# Mem_Switch_V1_0.net
KiCad netlist of a schematic drawn in EAGLE
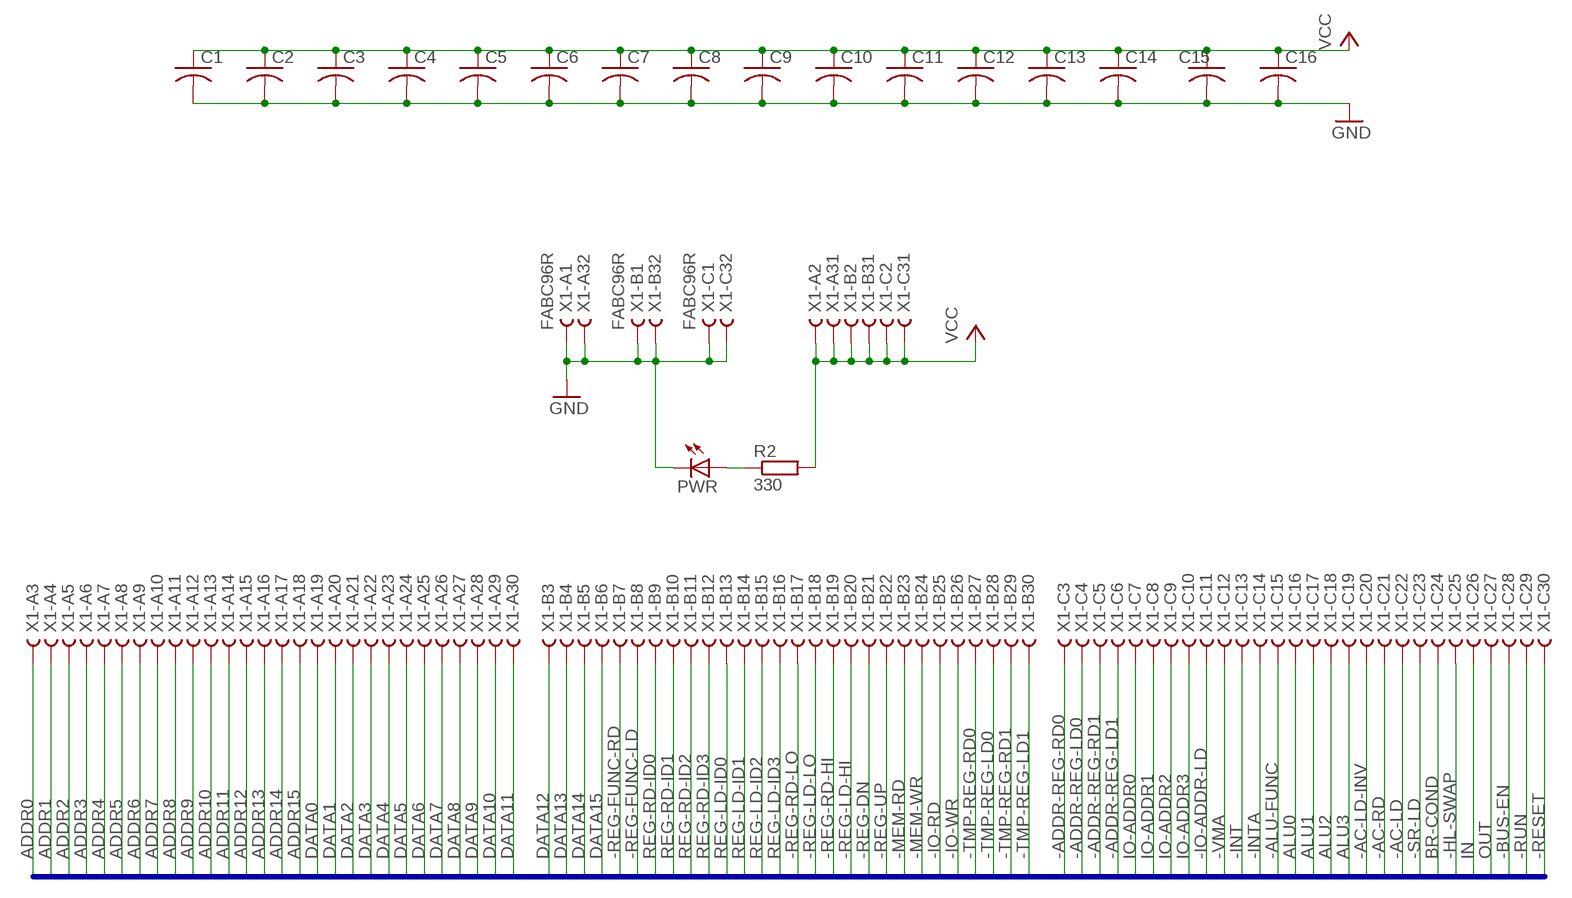
[diagram p0: schematic, sheet 1]
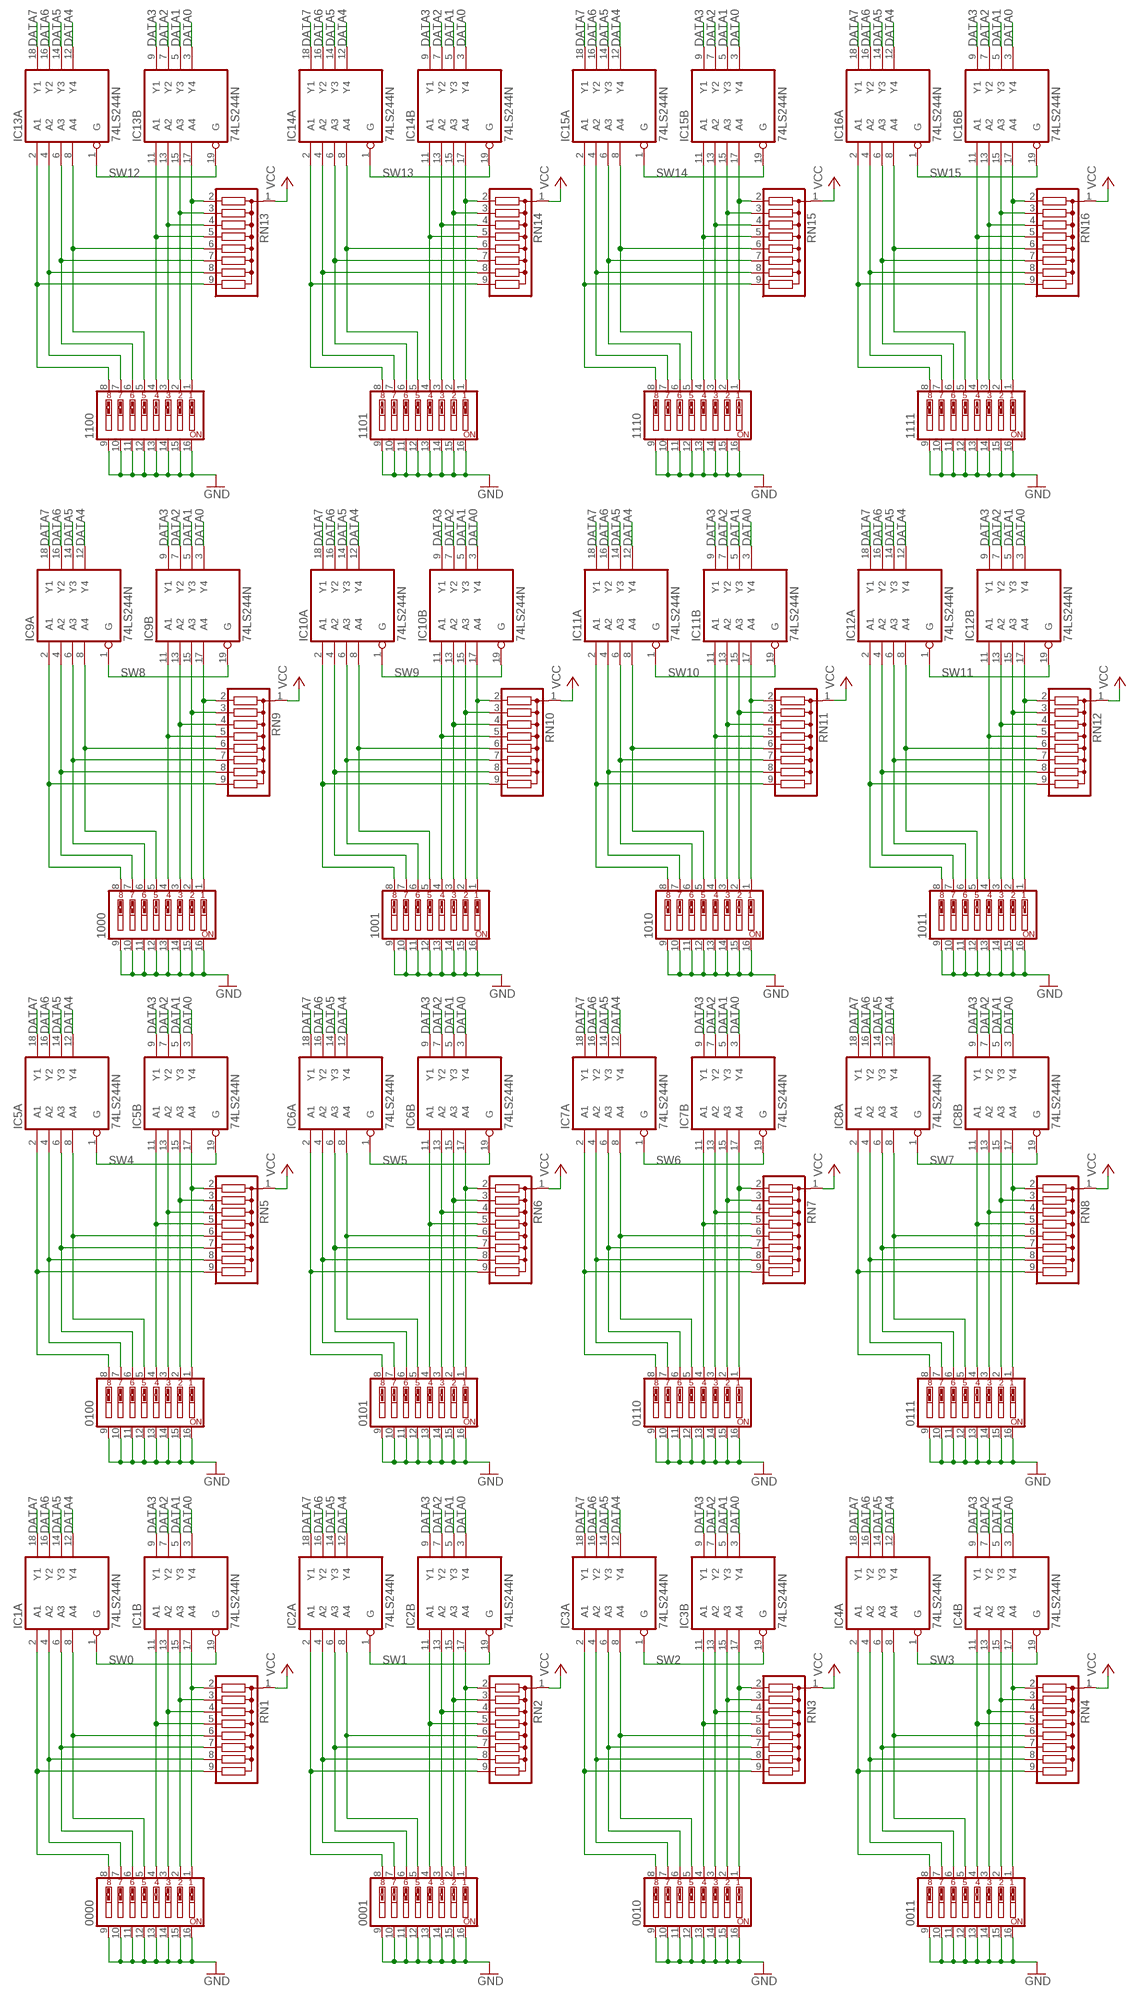
[diagram p1: schematic, sheet 2]
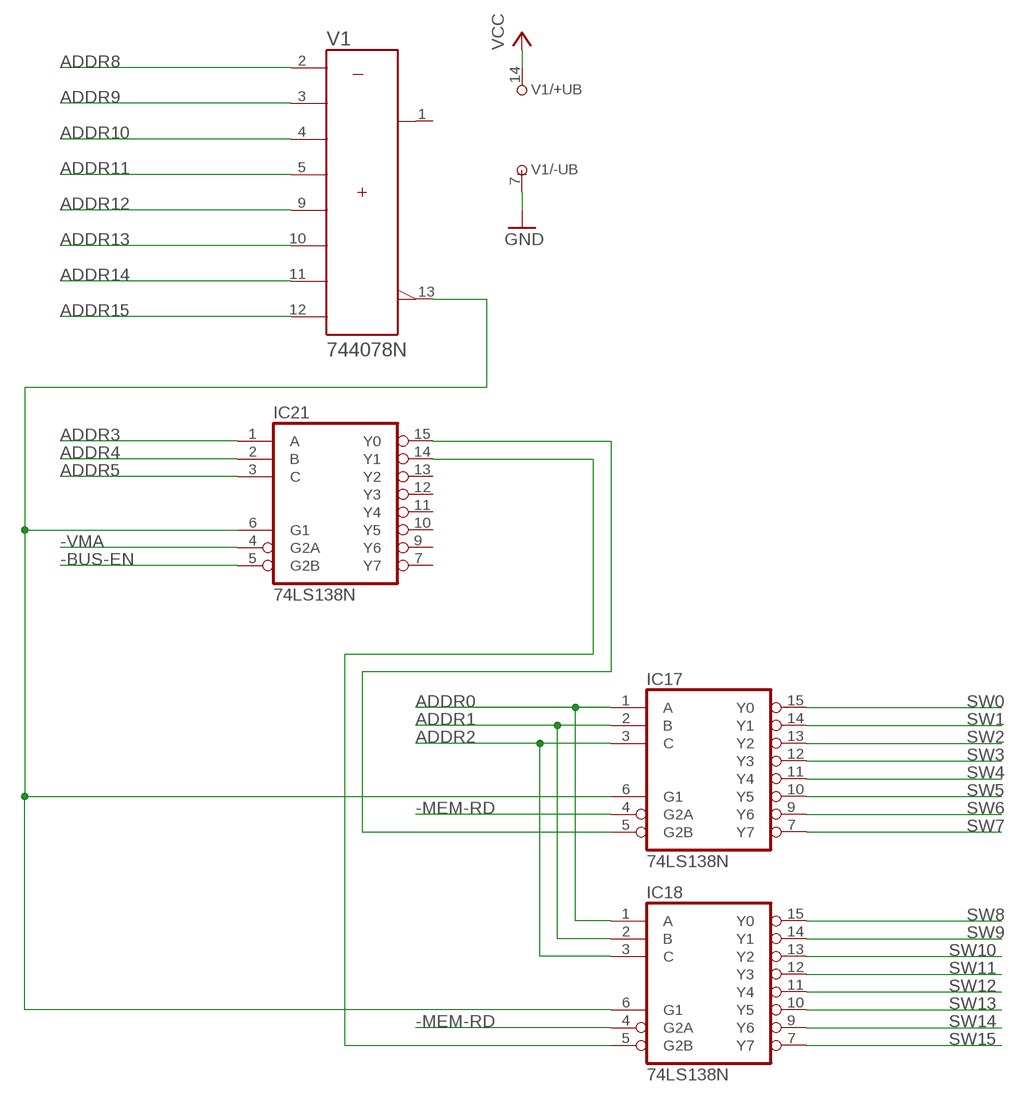
[diagram p2: schematic, sheet 3]

(export (version "E")
  (design (tool "Eeschema 10.0.6"))
  (components
    (comp (ref "C1")
      (value "C-US025-025X050")
      (footprint "eagle-import:C025-025X050")
      (libsource (lib "eagle-import") (part "C-US025-025X050"))
    )
    (comp (ref "C2")
      (value "C-US025-025X050")
      (footprint "eagle-import:C025-025X050")
      (libsource (lib "eagle-import") (part "C-US025-025X050"))
    )
    (comp (ref "C3")
      (value "C-US025-025X050")
      (footprint "eagle-import:C025-025X050")
      (libsource (lib "eagle-import") (part "C-US025-025X050"))
    )
    (comp (ref "C4")
      (value "C-US025-025X050")
      (footprint "eagle-import:C025-025X050")
      (libsource (lib "eagle-import") (part "C-US025-025X050"))
    )
    (comp (ref "C5")
      (value "C-US025-025X050")
      (footprint "eagle-import:C025-025X050")
      (libsource (lib "eagle-import") (part "C-US025-025X050"))
    )
    (comp (ref "C6")
      (value "C-US025-025X050")
      (footprint "eagle-import:C025-025X050")
      (libsource (lib "eagle-import") (part "C-US025-025X050"))
    )
    (comp (ref "C7")
      (value "C-US025-025X050")
      (footprint "eagle-import:C025-025X050")
      (libsource (lib "eagle-import") (part "C-US025-025X050"))
    )
    (comp (ref "C8")
      (value "C-US025-025X050")
      (footprint "eagle-import:C025-025X050")
      (libsource (lib "eagle-import") (part "C-US025-025X050"))
    )
    (comp (ref "C9")
      (value "C-US025-025X050")
      (footprint "eagle-import:C025-025X050")
      (libsource (lib "eagle-import") (part "C-US025-025X050"))
    )
    (comp (ref "C10")
      (value "C-US025-025X050")
      (footprint "eagle-import:C025-025X050")
      (libsource (lib "eagle-import") (part "C-US025-025X050"))
    )
    (comp (ref "C11")
      (value "C-US025-025X050")
      (footprint "eagle-import:C025-025X050")
      (libsource (lib "eagle-import") (part "C-US025-025X050"))
    )
    (comp (ref "C12")
      (value "C-US025-025X050")
      (footprint "eagle-import:C025-025X050")
      (libsource (lib "eagle-import") (part "C-US025-025X050"))
    )
    (comp (ref "C13")
      (value "C-US025-025X050")
      (footprint "eagle-import:C025-025X050")
      (libsource (lib "eagle-import") (part "C-US025-025X050"))
    )
    (comp (ref "C14")
      (value "C-US025-025X050")
      (footprint "eagle-import:C025-025X050")
      (libsource (lib "eagle-import") (part "C-US025-025X050"))
    )
    (comp (ref "C15")
      (value "C-US025-025X050")
      (footprint "eagle-import:C025-025X050")
      (libsource (lib "eagle-import") (part "C-US025-025X050"))
    )
    (comp (ref "C16")
      (value "C-US025-025X050")
      (footprint "eagle-import:C025-025X050")
      (libsource (lib "eagle-import") (part "C-US025-025X050"))
    )
    (comp (ref "PWR")
      (value "LED5MM")
      (footprint "eagle-import:LED5MM")
      (libsource (lib "eagle-import") (part "LED5MM"))
    )
    (comp (ref "R2")
      (value "330")
      (footprint "eagle-import:0207_10")
      (libsource (lib "eagle-import") (part "R0207/10"))
    )
    (comp (ref "X1")
      (value "FABC96R")
      (footprint "eagle-import:FABC96R")
      (libsource (lib "eagle-import") (part "FABC96R"))
    )
    (comp (ref "0000")
      (value "SW_DIP-8")
      (footprint "eagle-import:EDG-08")
      (libsource (lib "eagle-import") (part "SW_DIP-8"))
    )
    (comp (ref "0001")
      (value "SW_DIP-8")
      (footprint "eagle-import:EDG-08")
      (libsource (lib "eagle-import") (part "SW_DIP-8"))
    )
    (comp (ref "0010")
      (value "SW_DIP-8")
      (footprint "eagle-import:EDG-08")
      (libsource (lib "eagle-import") (part "SW_DIP-8"))
    )
    (comp (ref "0011")
      (value "SW_DIP-8")
      (footprint "eagle-import:EDG-08")
      (libsource (lib "eagle-import") (part "SW_DIP-8"))
    )
    (comp (ref "0100")
      (value "SW_DIP-8")
      (footprint "eagle-import:EDG-08")
      (libsource (lib "eagle-import") (part "SW_DIP-8"))
    )
    (comp (ref "0101")
      (value "SW_DIP-8")
      (footprint "eagle-import:EDG-08")
      (libsource (lib "eagle-import") (part "SW_DIP-8"))
    )
    (comp (ref "0110")
      (value "SW_DIP-8")
      (footprint "eagle-import:EDG-08")
      (libsource (lib "eagle-import") (part "SW_DIP-8"))
    )
    (comp (ref "0111")
      (value "SW_DIP-8")
      (footprint "eagle-import:EDG-08")
      (libsource (lib "eagle-import") (part "SW_DIP-8"))
    )
    (comp (ref "1000")
      (value "SW_DIP-8")
      (footprint "eagle-import:EDG-08")
      (libsource (lib "eagle-import") (part "SW_DIP-8"))
    )
    (comp (ref "1001")
      (value "SW_DIP-8")
      (footprint "eagle-import:EDG-08")
      (libsource (lib "eagle-import") (part "SW_DIP-8"))
    )
    (comp (ref "1010")
      (value "SW_DIP-8")
      (footprint "eagle-import:EDG-08")
      (libsource (lib "eagle-import") (part "SW_DIP-8"))
    )
    (comp (ref "1011")
      (value "SW_DIP-8")
      (footprint "eagle-import:EDG-08")
      (libsource (lib "eagle-import") (part "SW_DIP-8"))
    )
    (comp (ref "1100")
      (value "SW_DIP-8")
      (footprint "eagle-import:EDG-08")
      (libsource (lib "eagle-import") (part "SW_DIP-8"))
    )
    (comp (ref "1101")
      (value "SW_DIP-8")
      (footprint "eagle-import:EDG-08")
      (libsource (lib "eagle-import") (part "SW_DIP-8"))
    )
    (comp (ref "1110")
      (value "SW_DIP-8")
      (footprint "eagle-import:EDG-08")
      (libsource (lib "eagle-import") (part "SW_DIP-8"))
    )
    (comp (ref "1111")
      (value "SW_DIP-8")
      (footprint "eagle-import:EDG-08")
      (libsource (lib "eagle-import") (part "SW_DIP-8"))
    )
    (comp (ref "IC1")
      (value "74LS244N")
      (footprint "eagle-import:DIL20")
      (libsource (lib "eagle-import") (part "74xx-us_88_74244NLS"))
    )
    (comp (ref "IC2")
      (value "74LS244N")
      (footprint "eagle-import:DIL20")
      (libsource (lib "eagle-import") (part "74xx-us_88_74244NLS"))
    )
    (comp (ref "IC3")
      (value "74LS244N")
      (footprint "eagle-import:DIL20")
      (libsource (lib "eagle-import") (part "74xx-us_88_74244NLS"))
    )
    (comp (ref "IC4")
      (value "74LS244N")
      (footprint "eagle-import:DIL20")
      (libsource (lib "eagle-import") (part "74xx-us_88_74244NLS"))
    )
    (comp (ref "IC5")
      (value "74LS244N")
      (footprint "eagle-import:DIL20")
      (libsource (lib "eagle-import") (part "74xx-us_88_74244NLS"))
    )
    (comp (ref "IC6")
      (value "74LS244N")
      (footprint "eagle-import:DIL20")
      (libsource (lib "eagle-import") (part "74xx-us_88_74244NLS"))
    )
    (comp (ref "IC7")
      (value "74LS244N")
      (footprint "eagle-import:DIL20")
      (libsource (lib "eagle-import") (part "74xx-us_88_74244NLS"))
    )
    (comp (ref "IC8")
      (value "74LS244N")
      (footprint "eagle-import:DIL20")
      (libsource (lib "eagle-import") (part "74xx-us_88_74244NLS"))
    )
    (comp (ref "IC9")
      (value "74LS244N")
      (footprint "eagle-import:DIL20")
      (libsource (lib "eagle-import") (part "74xx-us_88_74244NLS"))
    )
    (comp (ref "IC10")
      (value "74LS244N")
      (footprint "eagle-import:DIL20")
      (libsource (lib "eagle-import") (part "74xx-us_88_74244NLS"))
    )
    (comp (ref "IC11")
      (value "74LS244N")
      (footprint "eagle-import:DIL20")
      (libsource (lib "eagle-import") (part "74xx-us_88_74244NLS"))
    )
    (comp (ref "IC12")
      (value "74LS244N")
      (footprint "eagle-import:DIL20")
      (libsource (lib "eagle-import") (part "74xx-us_88_74244NLS"))
    )
    (comp (ref "IC13")
      (value "74LS244N")
      (footprint "eagle-import:DIL20")
      (libsource (lib "eagle-import") (part "74xx-us_88_74244NLS"))
    )
    (comp (ref "IC14")
      (value "74LS244N")
      (footprint "eagle-import:DIL20")
      (libsource (lib "eagle-import") (part "74xx-us_88_74244NLS"))
    )
    (comp (ref "IC15")
      (value "74LS244N")
      (footprint "eagle-import:DIL20")
      (libsource (lib "eagle-import") (part "74xx-us_88_74244NLS"))
    )
    (comp (ref "IC16")
      (value "74LS244N")
      (footprint "eagle-import:DIL20")
      (libsource (lib "eagle-import") (part "74xx-us_88_74244NLS"))
    )
    (comp (ref "RN1")
      (value "G08R")
      (footprint "eagle-import:SIL9")
      (libsource (lib "eagle-import") (part "G08R"))
    )
    (comp (ref "RN2")
      (value "G08R")
      (footprint "eagle-import:SIL9")
      (libsource (lib "eagle-import") (part "G08R"))
    )
    (comp (ref "RN3")
      (value "G08R")
      (footprint "eagle-import:SIL9")
      (libsource (lib "eagle-import") (part "G08R"))
    )
    (comp (ref "RN4")
      (value "G08R")
      (footprint "eagle-import:SIL9")
      (libsource (lib "eagle-import") (part "G08R"))
    )
    (comp (ref "RN5")
      (value "G08R")
      (footprint "eagle-import:SIL9")
      (libsource (lib "eagle-import") (part "G08R"))
    )
    (comp (ref "RN6")
      (value "G08R")
      (footprint "eagle-import:SIL9")
      (libsource (lib "eagle-import") (part "G08R"))
    )
    (comp (ref "RN7")
      (value "G08R")
      (footprint "eagle-import:SIL9")
      (libsource (lib "eagle-import") (part "G08R"))
    )
    (comp (ref "RN8")
      (value "G08R")
      (footprint "eagle-import:SIL9")
      (libsource (lib "eagle-import") (part "G08R"))
    )
    (comp (ref "RN9")
      (value "G08R")
      (footprint "eagle-import:SIL9")
      (libsource (lib "eagle-import") (part "G08R"))
    )
    (comp (ref "RN10")
      (value "G08R")
      (footprint "eagle-import:SIL9")
      (libsource (lib "eagle-import") (part "G08R"))
    )
    (comp (ref "RN11")
      (value "G08R")
      (footprint "eagle-import:SIL9")
      (libsource (lib "eagle-import") (part "G08R"))
    )
    (comp (ref "RN12")
      (value "G08R")
      (footprint "eagle-import:SIL9")
      (libsource (lib "eagle-import") (part "G08R"))
    )
    (comp (ref "RN13")
      (value "G08R")
      (footprint "eagle-import:SIL9")
      (libsource (lib "eagle-import") (part "G08R"))
    )
    (comp (ref "RN14")
      (value "G08R")
      (footprint "eagle-import:SIL9")
      (libsource (lib "eagle-import") (part "G08R"))
    )
    (comp (ref "RN15")
      (value "G08R")
      (footprint "eagle-import:SIL9")
      (libsource (lib "eagle-import") (part "G08R"))
    )
    (comp (ref "RN16")
      (value "G08R")
      (footprint "eagle-import:SIL9")
      (libsource (lib "eagle-import") (part "G08R"))
    )
    (comp (ref "IC17")
      (value "74LS138N")
      (footprint "eagle-import:DIL16")
      (libsource (lib "eagle-import") (part "74138NLS"))
    )
    (comp (ref "IC18")
      (value "74LS138N")
      (footprint "eagle-import:DIL16")
      (libsource (lib "eagle-import") (part "74138NLS"))
    )
    (comp (ref "IC21")
      (value "74LS138N")
      (footprint "eagle-import:DIL16")
      (libsource (lib "eagle-import") (part "74138NLS"))
    )
    (comp (ref "V1")
      (value "744078N")
      (footprint "eagle-import:DIL14")
      (libsource (lib "eagle-import") (part "744078N"))
    )
  )
  (nets
    (net (code "1") (name "-AC-LD") (class "Default")
      (node (ref "X1") (pin "C22") (pinfunction "B_C22") (pintype "passive"))
    )
    (net (code "2") (name "-AC-LD-INV") (class "Default")
      (node (ref "X1") (pin "C20") (pinfunction "B_C20") (pintype "passive"))
    )
    (net (code "3") (name "-AC-RD") (class "Default")
      (node (ref "X1") (pin "C21") (pinfunction "B_C21") (pintype "passive"))
    )
    (net (code "4") (name "-ADDR-REG-LD0") (class "Default")
      (node (ref "X1") (pin "C4") (pinfunction "B_C4") (pintype "passive"))
    )
    (net (code "5") (name "-ADDR-REG-LD1") (class "Default")
      (node (ref "X1") (pin "C6") (pinfunction "B_C6") (pintype "passive"))
    )
    (net (code "6") (name "-ADDR-REG-RD0") (class "Default")
      (node (ref "X1") (pin "C3") (pinfunction "B_C3") (pintype "passive"))
    )
    (net (code "7") (name "-ADDR-REG-RD1") (class "Default")
      (node (ref "X1") (pin "C5") (pinfunction "B_C5") (pintype "passive"))
    )
    (net (code "8") (name "-ALU-FUNC") (class "Default")
      (node (ref "X1") (pin "C15") (pinfunction "B_C15") (pintype "passive"))
    )
    (net (code "9") (name "-BUS-EN") (class "Default")
      (node (ref "IC21") (pin "5") (pinfunction "G2B_5") (pintype "input"))
      (node (ref "X1") (pin "C28") (pinfunction "B_C28") (pintype "passive"))
    )
    (net (code "10") (name "-HL-SWAP") (class "Default")
      (node (ref "X1") (pin "C25") (pinfunction "B_C25") (pintype "passive"))
    )
    (net (code "11") (name "-INT") (class "Default")
      (node (ref "X1") (pin "C13") (pinfunction "B_C13") (pintype "passive"))
    )
    (net (code "12") (name "-INTA") (class "Default")
      (node (ref "X1") (pin "C14") (pinfunction "B_C14") (pintype "passive"))
    )
    (net (code "13") (name "-IO-ADDR-LD") (class "Default")
      (node (ref "X1") (pin "C11") (pinfunction "B_C11") (pintype "passive"))
    )
    (net (code "14") (name "-IO-RD") (class "Default")
      (node (ref "X1") (pin "B25") (pinfunction "B_B25") (pintype "passive"))
    )
    (net (code "15") (name "-IO-WR") (class "Default")
      (node (ref "X1") (pin "B26") (pinfunction "B_B26") (pintype "passive"))
    )
    (net (code "16") (name "-MEM-RD") (class "Default")
      (node (ref "IC17") (pin "4") (pinfunction "G2A_4") (pintype "input"))
      (node (ref "IC18") (pin "4") (pinfunction "G2A_4") (pintype "input"))
      (node (ref "X1") (pin "B23") (pinfunction "B_B23") (pintype "passive"))
    )
    (net (code "17") (name "-MEM-WR") (class "Default")
      (node (ref "X1") (pin "B24") (pinfunction "B_B24") (pintype "passive"))
    )
    (net (code "18") (name "-REG-DN") (class "Default")
      (node (ref "X1") (pin "B21") (pinfunction "B_B21") (pintype "passive"))
    )
    (net (code "19") (name "-REG-FUNC-LD") (class "Default")
      (node (ref "X1") (pin "B8") (pinfunction "B_B8") (pintype "passive"))
    )
    (net (code "20") (name "-REG-FUNC-RD") (class "Default")
      (node (ref "X1") (pin "B7") (pinfunction "B_B7") (pintype "passive"))
    )
    (net (code "21") (name "-REG-LD-HI") (class "Default")
      (node (ref "X1") (pin "B20") (pinfunction "B_B20") (pintype "passive"))
    )
    (net (code "22") (name "-REG-LD-LO") (class "Default")
      (node (ref "X1") (pin "B18") (pinfunction "B_B18") (pintype "passive"))
    )
    (net (code "23") (name "-REG-RD-HI") (class "Default")
      (node (ref "X1") (pin "B19") (pinfunction "B_B19") (pintype "passive"))
    )
    (net (code "24") (name "-REG-RD-LO") (class "Default")
      (node (ref "X1") (pin "B17") (pinfunction "B_B17") (pintype "passive"))
    )
    (net (code "25") (name "-REG-UP") (class "Default")
      (node (ref "X1") (pin "B22") (pinfunction "B_B22") (pintype "passive"))
    )
    (net (code "26") (name "-RESET") (class "Default")
      (node (ref "X1") (pin "C30") (pinfunction "B_C30") (pintype "passive"))
    )
    (net (code "27") (name "-RUN") (class "Default")
      (node (ref "X1") (pin "C29") (pinfunction "B_C29") (pintype "passive"))
    )
    (net (code "28") (name "-SR-LD") (class "Default")
      (node (ref "X1") (pin "C23") (pinfunction "B_C23") (pintype "passive"))
    )
    (net (code "29") (name "-TMP-REG-LD0") (class "Default")
      (node (ref "X1") (pin "B28") (pinfunction "B_B28") (pintype "passive"))
    )
    (net (code "30") (name "-TMP-REG-LD1") (class "Default")
      (node (ref "X1") (pin "B30") (pinfunction "B_B30") (pintype "passive"))
    )
    (net (code "31") (name "-TMP-REG-RD0") (class "Default")
      (node (ref "X1") (pin "B27") (pinfunction "B_B27") (pintype "passive"))
    )
    (net (code "32") (name "-TMP-REG-RD1") (class "Default")
      (node (ref "X1") (pin "B29") (pinfunction "B_B29") (pintype "passive"))
    )
    (net (code "33") (name "-VMA") (class "Default")
      (node (ref "IC21") (pin "4") (pinfunction "G2A_4") (pintype "input"))
      (node (ref "X1") (pin "C12") (pinfunction "B_C12") (pintype "passive"))
    )
    (net (code "34") (name "ADDR0") (class "Default")
      (node (ref "IC17") (pin "1") (pinfunction "A_1") (pintype "input"))
      (node (ref "IC18") (pin "1") (pinfunction "A_1") (pintype "input"))
      (node (ref "X1") (pin "A3") (pinfunction "B_A3") (pintype "passive"))
    )
    (net (code "35") (name "ADDR1") (class "Default")
      (node (ref "IC17") (pin "2") (pinfunction "B_2") (pintype "input"))
      (node (ref "IC18") (pin "2") (pinfunction "B_2") (pintype "input"))
      (node (ref "X1") (pin "A4") (pinfunction "B_A4") (pintype "passive"))
    )
    (net (code "36") (name "ADDR2") (class "Default")
      (node (ref "IC17") (pin "3") (pinfunction "C_3") (pintype "input"))
      (node (ref "IC18") (pin "3") (pinfunction "C_3") (pintype "input"))
      (node (ref "X1") (pin "A5") (pinfunction "B_A5") (pintype "passive"))
    )
    (net (code "37") (name "ADDR3") (class "Default")
      (node (ref "IC21") (pin "1") (pinfunction "A_1") (pintype "input"))
      (node (ref "X1") (pin "A6") (pinfunction "B_A6") (pintype "passive"))
    )
    (net (code "38") (name "ADDR4") (class "Default")
      (node (ref "IC21") (pin "2") (pinfunction "B_2") (pintype "input"))
      (node (ref "X1") (pin "A7") (pinfunction "B_A7") (pintype "passive"))
    )
    (net (code "39") (name "ADDR5") (class "Default")
      (node (ref "IC21") (pin "3") (pinfunction "C_3") (pintype "input"))
      (node (ref "X1") (pin "A8") (pinfunction "B_A8") (pintype "passive"))
    )
    (net (code "40") (name "ADDR6") (class "Default")
      (node (ref "X1") (pin "A9") (pinfunction "B_A9") (pintype "passive"))
    )
    (net (code "41") (name "ADDR7") (class "Default")
      (node (ref "X1") (pin "A10") (pinfunction "B_A10") (pintype "passive"))
    )
    (net (code "42") (name "ADDR8") (class "Default")
      (node (ref "V1") (pin "2") (pinfunction "A_2") (pintype "input"))
      (node (ref "X1") (pin "A11") (pinfunction "B_A11") (pintype "passive"))
    )
    (net (code "43") (name "ADDR9") (class "Default")
      (node (ref "V1") (pin "3") (pinfunction "B_3") (pintype "input"))
      (node (ref "X1") (pin "A12") (pinfunction "B_A12") (pintype "passive"))
    )
    (net (code "44") (name "ADDR10") (class "Default")
      (node (ref "V1") (pin "4") (pinfunction "C_4") (pintype "input"))
      (node (ref "X1") (pin "A13") (pinfunction "B_A13") (pintype "passive"))
    )
    (net (code "45") (name "ADDR11") (class "Default")
      (node (ref "V1") (pin "5") (pinfunction "D_5") (pintype "input"))
      (node (ref "X1") (pin "A14") (pinfunction "B_A14") (pintype "passive"))
    )
    (net (code "46") (name "ADDR12") (class "Default")
      (node (ref "V1") (pin "9") (pinfunction "E_9") (pintype "input"))
      (node (ref "X1") (pin "A15") (pinfunction "B_A15") (pintype "passive"))
    )
    (net (code "47") (name "ADDR13") (class "Default")
      (node (ref "V1") (pin "10") (pinfunction "F_10") (pintype "input"))
      (node (ref "X1") (pin "A16") (pinfunction "B_A16") (pintype "passive"))
    )
    (net (code "48") (name "ADDR14") (class "Default")
      (node (ref "V1") (pin "11") (pinfunction "G_11") (pintype "input"))
      (node (ref "X1") (pin "A17") (pinfunction "B_A17") (pintype "passive"))
    )
    (net (code "49") (name "ADDR15") (class "Default")
      (node (ref "V1") (pin "12") (pinfunction "H_12") (pintype "input"))
      (node (ref "X1") (pin "A18") (pinfunction "B_A18") (pintype "passive"))
    )
    (net (code "50") (name "ALU0") (class "Default")
      (node (ref "X1") (pin "C16") (pinfunction "B_C16") (pintype "passive"))
    )
    (net (code "51") (name "ALU1") (class "Default")
      (node (ref "X1") (pin "C17") (pinfunction "B_C17") (pintype "passive"))
    )
    (net (code "52") (name "ALU2") (class "Default")
      (node (ref "X1") (pin "C18") (pinfunction "B_C18") (pintype "passive"))
    )
    (net (code "53") (name "ALU3") (class "Default")
      (node (ref "X1") (pin "C19") (pinfunction "B_C19") (pintype "passive"))
    )
    (net (code "54") (name "BR-COND") (class "Default")
      (node (ref "X1") (pin "C24") (pinfunction "B_C24") (pintype "passive"))
    )
    (net (code "55") (name "DATA0") (class "Default")
      (node (ref "IC1") (pin "3") (pinfunction "Y4_3") (pintype "tri_state"))
      (node (ref "IC10") (pin "3") (pinfunction "Y4_3") (pintype "tri_state"))
      (node (ref "IC11") (pin "3") (pinfunction "Y4_3") (pintype "tri_state"))
      (node (ref "IC12") (pin "3") (pinfunction "Y4_3") (pintype "tri_state"))
      (node (ref "IC13") (pin "3") (pinfunction "Y4_3") (pintype "tri_state"))
      (node (ref "IC14") (pin "3") (pinfunction "Y4_3") (pintype "tri_state"))
      (node (ref "IC15") (pin "3") (pinfunction "Y4_3") (pintype "tri_state"))
      (node (ref "IC16") (pin "3") (pinfunction "Y4_3") (pintype "tri_state"))
      (node (ref "IC2") (pin "3") (pinfunction "Y4_3") (pintype "tri_state"))
      (node (ref "IC3") (pin "3") (pinfunction "Y4_3") (pintype "tri_state"))
      (node (ref "IC4") (pin "3") (pinfunction "Y4_3") (pintype "tri_state"))
      (node (ref "IC5") (pin "3") (pinfunction "Y4_3") (pintype "tri_state"))
      (node (ref "IC6") (pin "3") (pinfunction "Y4_3") (pintype "tri_state"))
      (node (ref "IC7") (pin "3") (pinfunction "Y4_3") (pintype "tri_state"))
      (node (ref "IC8") (pin "3") (pinfunction "Y4_3") (pintype "tri_state"))
      (node (ref "IC9") (pin "3") (pinfunction "Y4_3") (pintype "tri_state"))
      (node (ref "X1") (pin "A19") (pinfunction "B_A19") (pintype "passive"))
    )
    (net (code "56") (name "DATA1") (class "Default")
      (node (ref "IC1") (pin "5") (pinfunction "Y3_5") (pintype "tri_state"))
      (node (ref "IC10") (pin "5") (pinfunction "Y3_5") (pintype "tri_state"))
      (node (ref "IC11") (pin "5") (pinfunction "Y3_5") (pintype "tri_state"))
      (node (ref "IC12") (pin "5") (pinfunction "Y3_5") (pintype "tri_state"))
      (node (ref "IC13") (pin "5") (pinfunction "Y3_5") (pintype "tri_state"))
      (node (ref "IC14") (pin "5") (pinfunction "Y3_5") (pintype "tri_state"))
      (node (ref "IC15") (pin "5") (pinfunction "Y3_5") (pintype "tri_state"))
      (node (ref "IC16") (pin "5") (pinfunction "Y3_5") (pintype "tri_state"))
      (node (ref "IC2") (pin "5") (pinfunction "Y3_5") (pintype "tri_state"))
      (node (ref "IC3") (pin "5") (pinfunction "Y3_5") (pintype "tri_state"))
      (node (ref "IC4") (pin "5") (pinfunction "Y3_5") (pintype "tri_state"))
      (node (ref "IC5") (pin "5") (pinfunction "Y3_5") (pintype "tri_state"))
      (node (ref "IC6") (pin "5") (pinfunction "Y3_5") (pintype "tri_state"))
      (node (ref "IC7") (pin "5") (pinfunction "Y3_5") (pintype "tri_state"))
      (node (ref "IC8") (pin "5") (pinfunction "Y3_5") (pintype "tri_state"))
      (node (ref "IC9") (pin "5") (pinfunction "Y3_5") (pintype "tri_state"))
      (node (ref "X1") (pin "A20") (pinfunction "B_A20") (pintype "passive"))
    )
    (net (code "57") (name "DATA2") (class "Default")
      (node (ref "IC1") (pin "7") (pinfunction "Y2_7") (pintype "tri_state"))
      (node (ref "IC10") (pin "7") (pinfunction "Y2_7") (pintype "tri_state"))
      (node (ref "IC11") (pin "7") (pinfunction "Y2_7") (pintype "tri_state"))
      (node (ref "IC12") (pin "7") (pinfunction "Y2_7") (pintype "tri_state"))
      (node (ref "IC13") (pin "7") (pinfunction "Y2_7") (pintype "tri_state"))
      (node (ref "IC14") (pin "7") (pinfunction "Y2_7") (pintype "tri_state"))
      (node (ref "IC15") (pin "7") (pinfunction "Y2_7") (pintype "tri_state"))
      (node (ref "IC16") (pin "7") (pinfunction "Y2_7") (pintype "tri_state"))
      (node (ref "IC2") (pin "7") (pinfunction "Y2_7") (pintype "tri_state"))
      (node (ref "IC3") (pin "7") (pinfunction "Y2_7") (pintype "tri_state"))
      (node (ref "IC4") (pin "7") (pinfunction "Y2_7") (pintype "tri_state"))
      (node (ref "IC5") (pin "7") (pinfunction "Y2_7") (pintype "tri_state"))
      (node (ref "IC6") (pin "7") (pinfunction "Y2_7") (pintype "tri_state"))
      (node (ref "IC7") (pin "7") (pinfunction "Y2_7") (pintype "tri_state"))
      (node (ref "IC8") (pin "7") (pinfunction "Y2_7") (pintype "tri_state"))
      (node (ref "IC9") (pin "7") (pinfunction "Y2_7") (pintype "tri_state"))
      (node (ref "X1") (pin "A21") (pinfunction "B_A21") (pintype "passive"))
    )
    (net (code "58") (name "DATA3") (class "Default")
      (node (ref "IC1") (pin "9") (pinfunction "Y1_9") (pintype "tri_state"))
      (node (ref "IC10") (pin "9") (pinfunction "Y1_9") (pintype "tri_state"))
      (node (ref "IC11") (pin "9") (pinfunction "Y1_9") (pintype "tri_state"))
      (node (ref "IC12") (pin "9") (pinfunction "Y1_9") (pintype "tri_state"))
      (node (ref "IC13") (pin "9") (pinfunction "Y1_9") (pintype "tri_state"))
      (node (ref "IC14") (pin "9") (pinfunction "Y1_9") (pintype "tri_state"))
      (node (ref "IC15") (pin "9") (pinfunction "Y1_9") (pintype "tri_state"))
      (node (ref "IC16") (pin "9") (pinfunction "Y1_9") (pintype "tri_state"))
      (node (ref "IC2") (pin "9") (pinfunction "Y1_9") (pintype "tri_state"))
      (node (ref "IC3") (pin "9") (pinfunction "Y1_9") (pintype "tri_state"))
      (node (ref "IC4") (pin "9") (pinfunction "Y1_9") (pintype "tri_state"))
      (node (ref "IC5") (pin "9") (pinfunction "Y1_9") (pintype "tri_state"))
      (node (ref "IC6") (pin "9") (pinfunction "Y1_9") (pintype "tri_state"))
      (node (ref "IC7") (pin "9") (pinfunction "Y1_9") (pintype "tri_state"))
      (node (ref "IC8") (pin "9") (pinfunction "Y1_9") (pintype "tri_state"))
      (node (ref "IC9") (pin "9") (pinfunction "Y1_9") (pintype "tri_state"))
      (node (ref "X1") (pin "A22") (pinfunction "B_A22") (pintype "passive"))
    )
    (net (code "59") (name "DATA4") (class "Default")
      (node (ref "IC1") (pin "12") (pinfunction "Y4_12") (pintype "tri_state"))
      (node (ref "IC10") (pin "12") (pinfunction "Y4_12") (pintype "tri_state"))
      (node (ref "IC11") (pin "12") (pinfunction "Y4_12") (pintype "tri_state"))
      (node (ref "IC12") (pin "12") (pinfunction "Y4_12") (pintype "tri_state"))
      (node (ref "IC13") (pin "12") (pinfunction "Y4_12") (pintype "tri_state"))
      (node (ref "IC14") (pin "12") (pinfunction "Y4_12") (pintype "tri_state"))
      (node (ref "IC15") (pin "12") (pinfunction "Y4_12") (pintype "tri_state"))
      (node (ref "IC16") (pin "12") (pinfunction "Y4_12") (pintype "tri_state"))
      (node (ref "IC2") (pin "12") (pinfunction "Y4_12") (pintype "tri_state"))
      (node (ref "IC3") (pin "12") (pinfunction "Y4_12") (pintype "tri_state"))
      (node (ref "IC4") (pin "12") (pinfunction "Y4_12") (pintype "tri_state"))
      (node (ref "IC5") (pin "12") (pinfunction "Y4_12") (pintype "tri_state"))
      (node (ref "IC6") (pin "12") (pinfunction "Y4_12") (pintype "tri_state"))
      (node (ref "IC7") (pin "12") (pinfunction "Y4_12") (pintype "tri_state"))
      (node (ref "IC8") (pin "12") (pinfunction "Y4_12") (pintype "tri_state"))
      (node (ref "IC9") (pin "12") (pinfunction "Y4_12") (pintype "tri_state"))
      (node (ref "X1") (pin "A23") (pinfunction "B_A23") (pintype "passive"))
    )
    (net (code "60") (name "DATA5") (class "Default")
      (node (ref "IC1") (pin "14") (pinfunction "Y3_14") (pintype "tri_state"))
      (node (ref "IC10") (pin "14") (pinfunction "Y3_14") (pintype "tri_state"))
      (node (ref "IC11") (pin "14") (pinfunction "Y3_14") (pintype "tri_state"))
      (node (ref "IC12") (pin "14") (pinfunction "Y3_14") (pintype "tri_state"))
      (node (ref "IC13") (pin "14") (pinfunction "Y3_14") (pintype "tri_state"))
      (node (ref "IC14") (pin "14") (pinfunction "Y3_14") (pintype "tri_state"))
      (node (ref "IC15") (pin "14") (pinfunction "Y3_14") (pintype "tri_state"))
      (node (ref "IC16") (pin "14") (pinfunction "Y3_14") (pintype "tri_state"))
      (node (ref "IC2") (pin "14") (pinfunction "Y3_14") (pintype "tri_state"))
      (node (ref "IC3") (pin "14") (pinfunction "Y3_14") (pintype "tri_state"))
      (node (ref "IC4") (pin "14") (pinfunction "Y3_14") (pintype "tri_state"))
      (node (ref "IC5") (pin "14") (pinfunction "Y3_14") (pintype "tri_state"))
      (node (ref "IC6") (pin "14") (pinfunction "Y3_14") (pintype "tri_state"))
      (node (ref "IC7") (pin "14") (pinfunction "Y3_14") (pintype "tri_state"))
      (node (ref "IC8") (pin "14") (pinfunction "Y3_14") (pintype "tri_state"))
      (node (ref "IC9") (pin "14") (pinfunction "Y3_14") (pintype "tri_state"))
      (node (ref "X1") (pin "A24") (pinfunction "B_A24") (pintype "passive"))
    )
    (net (code "61") (name "DATA6") (class "Default")
      (node (ref "IC1") (pin "16") (pinfunction "Y2_16") (pintype "tri_state"))
      (node (ref "IC10") (pin "16") (pinfunction "Y2_16") (pintype "tri_state"))
      (node (ref "IC11") (pin "16") (pinfunction "Y2_16") (pintype "tri_state"))
      (node (ref "IC12") (pin "16") (pinfunction "Y2_16") (pintype "tri_state"))
      (node (ref "IC13") (pin "16") (pinfunction "Y2_16") (pintype "tri_state"))
      (node (ref "IC14") (pin "16") (pinfunction "Y2_16") (pintype "tri_state"))
      (node (ref "IC15") (pin "16") (pinfunction "Y2_16") (pintype "tri_state"))
      (node (ref "IC16") (pin "16") (pinfunction "Y2_16") (pintype "tri_state"))
      (node (ref "IC2") (pin "16") (pinfunction "Y2_16") (pintype "tri_state"))
      (node (ref "IC3") (pin "16") (pinfunction "Y2_16") (pintype "tri_state"))
      (node (ref "IC4") (pin "16") (pinfunction "Y2_16") (pintype "tri_state"))
      (node (ref "IC5") (pin "16") (pinfunction "Y2_16") (pintype "tri_state"))
      (node (ref "IC6") (pin "16") (pinfunction "Y2_16") (pintype "tri_state"))
      (node (ref "IC7") (pin "16") (pinfunction "Y2_16") (pintype "tri_state"))
      (node (ref "IC8") (pin "16") (pinfunction "Y2_16") (pintype "tri_state"))
      (node (ref "IC9") (pin "16") (pinfunction "Y2_16") (pintype "tri_state"))
      (node (ref "X1") (pin "A25") (pinfunction "B_A25") (pintype "passive"))
    )
    (net (code "62") (name "DATA7") (class "Default")
      (node (ref "IC1") (pin "18") (pinfunction "Y1_18") (pintype "tri_state"))
      (node (ref "IC10") (pin "18") (pinfunction "Y1_18") (pintype "tri_state"))
      (node (ref "IC11") (pin "18") (pinfunction "Y1_18") (pintype "tri_state"))
      (node (ref "IC12") (pin "18") (pinfunction "Y1_18") (pintype "tri_state"))
      (node (ref "IC13") (pin "18") (pinfunction "Y1_18") (pintype "tri_state"))
      (node (ref "IC14") (pin "18") (pinfunction "Y1_18") (pintype "tri_state"))
      (node (ref "IC15") (pin "18") (pinfunction "Y1_18") (pintype "tri_state"))
      (node (ref "IC16") (pin "18") (pinfunction "Y1_18") (pintype "tri_state"))
      (node (ref "IC2") (pin "18") (pinfunction "Y1_18") (pintype "tri_state"))
      (node (ref "IC3") (pin "18") (pinfunction "Y1_18") (pintype "tri_state"))
      (node (ref "IC4") (pin "18") (pinfunction "Y1_18") (pintype "tri_state"))
      (node (ref "IC5") (pin "18") (pinfunction "Y1_18") (pintype "tri_state"))
      (node (ref "IC6") (pin "18") (pinfunction "Y1_18") (pintype "tri_state"))
      (node (ref "IC7") (pin "18") (pinfunction "Y1_18") (pintype "tri_state"))
      (node (ref "IC8") (pin "18") (pinfunction "Y1_18") (pintype "tri_state"))
      (node (ref "IC9") (pin "18") (pinfunction "Y1_18") (pintype "tri_state"))
      (node (ref "X1") (pin "A26") (pinfunction "B_A26") (pintype "passive"))
    )
    (net (code "63") (name "DATA8") (class "Default")
      (node (ref "X1") (pin "A27") (pinfunction "B_A27") (pintype "passive"))
    )
    (net (code "64") (name "DATA9") (class "Default")
      (node (ref "X1") (pin "A28") (pinfunction "B_A28") (pintype "passive"))
    )
    (net (code "65") (name "DATA10") (class "Default")
      (node (ref "X1") (pin "A29") (pinfunction "B_A29") (pintype "passive"))
    )
    (net (code "66") (name "DATA11") (class "Default")
      (node (ref "X1") (pin "A30") (pinfunction "B_A30") (pintype "passive"))
    )
    (net (code "67") (name "DATA12") (class "Default")
      (node (ref "X1") (pin "B3") (pinfunction "B_B3") (pintype "passive"))
    )
    (net (code "68") (name "DATA13") (class "Default")
      (node (ref "X1") (pin "B4") (pinfunction "B_B4") (pintype "passive"))
    )
    (net (code "69") (name "DATA14") (class "Default")
      (node (ref "X1") (pin "B5") (pinfunction "B_B5") (pintype "passive"))
    )
    (net (code "70") (name "DATA15") (class "Default")
      (node (ref "X1") (pin "B6") (pinfunction "B_B6") (pintype "passive"))
    )
    (net (code "71") (name "GND") (class "Default")
      (node (ref "0000") (pin "10") (pinfunction "10_10") (pintype "passive"))
      (node (ref "0000") (pin "11") (pinfunction "11_11") (pintype "passive"))
      (node (ref "0000") (pin "12") (pinfunction "12_12") (pintype "passive"))
      (node (ref "0000") (pin "13") (pinfunction "13_13") (pintype "passive"))
      (node (ref "0000") (pin "14") (pinfunction "14_14") (pintype "passive"))
      (node (ref "0000") (pin "15") (pinfunction "15_15") (pintype "passive"))
      (node (ref "0000") (pin "16") (pinfunction "16_16") (pintype "passive"))
      (node (ref "0000") (pin "9") (pinfunction "9_9") (pintype "passive"))
      (node (ref "0001") (pin "10") (pinfunction "10_10") (pintype "passive"))
      (node (ref "0001") (pin "11") (pinfunction "11_11") (pintype "passive"))
      (node (ref "0001") (pin "12") (pinfunction "12_12") (pintype "passive"))
      (node (ref "0001") (pin "13") (pinfunction "13_13") (pintype "passive"))
      (node (ref "0001") (pin "14") (pinfunction "14_14") (pintype "passive"))
      (node (ref "0001") (pin "15") (pinfunction "15_15") (pintype "passive"))
      (node (ref "0001") (pin "16") (pinfunction "16_16") (pintype "passive"))
      (node (ref "0001") (pin "9") (pinfunction "9_9") (pintype "passive"))
      (node (ref "0010") (pin "10") (pinfunction "10_10") (pintype "passive"))
      (node (ref "0010") (pin "11") (pinfunction "11_11") (pintype "passive"))
      (node (ref "0010") (pin "12") (pinfunction "12_12") (pintype "passive"))
      (node (ref "0010") (pin "13") (pinfunction "13_13") (pintype "passive"))
      (node (ref "0010") (pin "14") (pinfunction "14_14") (pintype "passive"))
      (node (ref "0010") (pin "15") (pinfunction "15_15") (pintype "passive"))
      (node (ref "0010") (pin "16") (pinfunction "16_16") (pintype "passive"))
      (node (ref "0010") (pin "9") (pinfunction "9_9") (pintype "passive"))
      (node (ref "0011") (pin "10") (pinfunction "10_10") (pintype "passive"))
      (node (ref "0011") (pin "11") (pinfunction "11_11") (pintype "passive"))
      (node (ref "0011") (pin "12") (pinfunction "12_12") (pintype "passive"))
      (node (ref "0011") (pin "13") (pinfunction "13_13") (pintype "passive"))
      (node (ref "0011") (pin "14") (pinfunction "14_14") (pintype "passive"))
      (node (ref "0011") (pin "15") (pinfunction "15_15") (pintype "passive"))
      (node (ref "0011") (pin "16") (pinfunction "16_16") (pintype "passive"))
      (node (ref "0011") (pin "9") (pinfunction "9_9") (pintype "passive"))
      (node (ref "0100") (pin "10") (pinfunction "10_10") (pintype "passive"))
      (node (ref "0100") (pin "11") (pinfunction "11_11") (pintype "passive"))
      (node (ref "0100") (pin "12") (pinfunction "12_12") (pintype "passive"))
      (node (ref "0100") (pin "13") (pinfunction "13_13") (pintype "passive"))
      (node (ref "0100") (pin "14") (pinfunction "14_14") (pintype "passive"))
      (node (ref "0100") (pin "15") (pinfunction "15_15") (pintype "passive"))
      (node (ref "0100") (pin "16") (pinfunction "16_16") (pintype "passive"))
      (node (ref "0100") (pin "9") (pinfunction "9_9") (pintype "passive"))
      (node (ref "0101") (pin "10") (pinfunction "10_10") (pintype "passive"))
      (node (ref "0101") (pin "11") (pinfunction "11_11") (pintype "passive"))
      (node (ref "0101") (pin "12") (pinfunction "12_12") (pintype "passive"))
      (node (ref "0101") (pin "13") (pinfunction "13_13") (pintype "passive"))
      (node (ref "0101") (pin "14") (pinfunction "14_14") (pintype "passive"))
      (node (ref "0101") (pin "15") (pinfunction "15_15") (pintype "passive"))
      (node (ref "0101") (pin "16") (pinfunction "16_16") (pintype "passive"))
      (node (ref "0101") (pin "9") (pinfunction "9_9") (pintype "passive"))
      (node (ref "0110") (pin "10") (pinfunction "10_10") (pintype "passive"))
      (node (ref "0110") (pin "11") (pinfunction "11_11") (pintype "passive"))
      (node (ref "0110") (pin "12") (pinfunction "12_12") (pintype "passive"))
      (node (ref "0110") (pin "13") (pinfunction "13_13") (pintype "passive"))
      (node (ref "0110") (pin "14") (pinfunction "14_14") (pintype "passive"))
      (node (ref "0110") (pin "15") (pinfunction "15_15") (pintype "passive"))
      (node (ref "0110") (pin "16") (pinfunction "16_16") (pintype "passive"))
      (node (ref "0110") (pin "9") (pinfunction "9_9") (pintype "passive"))
      (node (ref "0111") (pin "10") (pinfunction "10_10") (pintype "passive"))
      (node (ref "0111") (pin "11") (pinfunction "11_11") (pintype "passive"))
      (node (ref "0111") (pin "12") (pinfunction "12_12") (pintype "passive"))
      (node (ref "0111") (pin "13") (pinfunction "13_13") (pintype "passive"))
      (node (ref "0111") (pin "14") (pinfunction "14_14") (pintype "passive"))
      (node (ref "0111") (pin "15") (pinfunction "15_15") (pintype "passive"))
      (node (ref "0111") (pin "16") (pinfunction "16_16") (pintype "passive"))
      (node (ref "0111") (pin "9") (pinfunction "9_9") (pintype "passive"))
      (node (ref "1000") (pin "10") (pinfunction "10_10") (pintype "passive"))
      (node (ref "1000") (pin "11") (pinfunction "11_11") (pintype "passive"))
      (node (ref "1000") (pin "12") (pinfunction "12_12") (pintype "passive"))
      (node (ref "1000") (pin "13") (pinfunction "13_13") (pintype "passive"))
      (node (ref "1000") (pin "14") (pinfunction "14_14") (pintype "passive"))
      (node (ref "1000") (pin "15") (pinfunction "15_15") (pintype "passive"))
      (node (ref "1000") (pin "16") (pinfunction "16_16") (pintype "passive"))
      (node (ref "1000") (pin "9") (pinfunction "9_9") (pintype "passive"))
      (node (ref "1001") (pin "10") (pinfunction "10_10") (pintype "passive"))
      (node (ref "1001") (pin "11") (pinfunction "11_11") (pintype "passive"))
      (node (ref "1001") (pin "12") (pinfunction "12_12") (pintype "passive"))
      (node (ref "1001") (pin "13") (pinfunction "13_13") (pintype "passive"))
      (node (ref "1001") (pin "14") (pinfunction "14_14") (pintype "passive"))
      (node (ref "1001") (pin "15") (pinfunction "15_15") (pintype "passive"))
      (node (ref "1001") (pin "16") (pinfunction "16_16") (pintype "passive"))
      (node (ref "1001") (pin "9") (pinfunction "9_9") (pintype "passive"))
      (node (ref "1010") (pin "10") (pinfunction "10_10") (pintype "passive"))
      (node (ref "1010") (pin "11") (pinfunction "11_11") (pintype "passive"))
      (node (ref "1010") (pin "12") (pinfunction "12_12") (pintype "passive"))
      (node (ref "1010") (pin "13") (pinfunction "13_13") (pintype "passive"))
      (node (ref "1010") (pin "14") (pinfunction "14_14") (pintype "passive"))
      (node (ref "1010") (pin "15") (pinfunction "15_15") (pintype "passive"))
      (node (ref "1010") (pin "16") (pinfunction "16_16") (pintype "passive"))
      (node (ref "1010") (pin "9") (pinfunction "9_9") (pintype "passive"))
      (node (ref "1011") (pin "10") (pinfunction "10_10") (pintype "passive"))
      (node (ref "1011") (pin "11") (pinfunction "11_11") (pintype "passive"))
      (node (ref "1011") (pin "12") (pinfunction "12_12") (pintype "passive"))
      (node (ref "1011") (pin "13") (pinfunction "13_13") (pintype "passive"))
      (node (ref "1011") (pin "14") (pinfunction "14_14") (pintype "passive"))
      (node (ref "1011") (pin "15") (pinfunction "15_15") (pintype "passive"))
      (node (ref "1011") (pin "16") (pinfunction "16_16") (pintype "passive"))
      (node (ref "1011") (pin "9") (pinfunction "9_9") (pintype "passive"))
      (node (ref "1100") (pin "10") (pinfunction "10_10") (pintype "passive"))
      (node (ref "1100") (pin "11") (pinfunction "11_11") (pintype "passive"))
      (node (ref "1100") (pin "12") (pinfunction "12_12") (pintype "passive"))
      (node (ref "1100") (pin "13") (pinfunction "13_13") (pintype "passive"))
      (node (ref "1100") (pin "14") (pinfunction "14_14") (pintype "passive"))
      (node (ref "1100") (pin "15") (pinfunction "15_15") (pintype "passive"))
      (node (ref "1100") (pin "16") (pinfunction "16_16") (pintype "passive"))
      (node (ref "1100") (pin "9") (pinfunction "9_9") (pintype "passive"))
      (node (ref "1101") (pin "10") (pinfunction "10_10") (pintype "passive"))
      (node (ref "1101") (pin "11") (pinfunction "11_11") (pintype "passive"))
      (node (ref "1101") (pin "12") (pinfunction "12_12") (pintype "passive"))
      (node (ref "1101") (pin "13") (pinfunction "13_13") (pintype "passive"))
      (node (ref "1101") (pin "14") (pinfunction "14_14") (pintype "passive"))
      (node (ref "1101") (pin "15") (pinfunction "15_15") (pintype "passive"))
      (node (ref "1101") (pin "16") (pinfunction "16_16") (pintype "passive"))
      (node (ref "1101") (pin "9") (pinfunction "9_9") (pintype "passive"))
      (node (ref "1110") (pin "10") (pinfunction "10_10") (pintype "passive"))
      (node (ref "1110") (pin "11") (pinfunction "11_11") (pintype "passive"))
      (node (ref "1110") (pin "12") (pinfunction "12_12") (pintype "passive"))
      (node (ref "1110") (pin "13") (pinfunction "13_13") (pintype "passive"))
      (node (ref "1110") (pin "14") (pinfunction "14_14") (pintype "passive"))
      (node (ref "1110") (pin "15") (pinfunction "15_15") (pintype "passive"))
      (node (ref "1110") (pin "16") (pinfunction "16_16") (pintype "passive"))
      (node (ref "1110") (pin "9") (pinfunction "9_9") (pintype "passive"))
      (node (ref "1111") (pin "10") (pinfunction "10_10") (pintype "passive"))
      (node (ref "1111") (pin "11") (pinfunction "11_11") (pintype "passive"))
      (node (ref "1111") (pin "12") (pinfunction "12_12") (pintype "passive"))
      (node (ref "1111") (pin "13") (pinfunction "13_13") (pintype "passive"))
      (node (ref "1111") (pin "14") (pinfunction "14_14") (pintype "passive"))
      (node (ref "1111") (pin "15") (pinfunction "15_15") (pintype "passive"))
      (node (ref "1111") (pin "16") (pinfunction "16_16") (pintype "passive"))
      (node (ref "1111") (pin "9") (pinfunction "9_9") (pintype "passive"))
      (node (ref "C1") (pin "2") (pinfunction "2_2") (pintype "passive"))
      (node (ref "C10") (pin "2") (pinfunction "2_2") (pintype "passive"))
      (node (ref "C11") (pin "2") (pinfunction "2_2") (pintype "passive"))
      (node (ref "C12") (pin "2") (pinfunction "2_2") (pintype "passive"))
      (node (ref "C13") (pin "2") (pinfunction "2_2") (pintype "passive"))
      (node (ref "C14") (pin "2") (pinfunction "2_2") (pintype "passive"))
      (node (ref "C15") (pin "2") (pinfunction "2_2") (pintype "passive"))
      (node (ref "C16") (pin "2") (pinfunction "2_2") (pintype "passive"))
      (node (ref "C2") (pin "2") (pinfunction "2_2") (pintype "passive"))
      (node (ref "C3") (pin "2") (pinfunction "2_2") (pintype "passive"))
      (node (ref "C4") (pin "2") (pinfunction "2_2") (pintype "passive"))
      (node (ref "C5") (pin "2") (pinfunction "2_2") (pintype "passive"))
      (node (ref "C6") (pin "2") (pinfunction "2_2") (pintype "passive"))
      (node (ref "C7") (pin "2") (pinfunction "2_2") (pintype "passive"))
      (node (ref "C8") (pin "2") (pinfunction "2_2") (pintype "passive"))
      (node (ref "C9") (pin "2") (pinfunction "2_2") (pintype "passive"))
      (node (ref "PWR") (pin "K") (pinfunction "C_K") (pintype "passive"))
      (node (ref "V1") (pin "7") (pinfunction "-UB_7") (pintype "power_in"))
      (node (ref "X1") (pin "A1") (pinfunction "B_A1") (pintype "passive"))
      (node (ref "X1") (pin "A32") (pinfunction "B_A32") (pintype "passive"))
      (node (ref "X1") (pin "B1") (pinfunction "B_B1") (pintype "passive"))
      (node (ref "X1") (pin "B32") (pinfunction "B_B32") (pintype "passive"))
      (node (ref "X1") (pin "C1") (pinfunction "B_C1") (pintype "passive"))
      (node (ref "X1") (pin "C32") (pinfunction "B_C32") (pintype "passive"))
    )
    (net (code "72") (name "IN") (class "Default")
      (node (ref "X1") (pin "C26") (pinfunction "B_C26") (pintype "passive"))
    )
    (net (code "73") (name "IO-ADDR0") (class "Default")
      (node (ref "X1") (pin "C7") (pinfunction "B_C7") (pintype "passive"))
    )
    (net (code "74") (name "IO-ADDR1") (class "Default")
      (node (ref "X1") (pin "C8") (pinfunction "B_C8") (pintype "passive"))
    )
    (net (code "75") (name "IO-ADDR2") (class "Default")
      (node (ref "X1") (pin "C9") (pinfunction "B_C9") (pintype "passive"))
    )
    (net (code "76") (name "IO-ADDR3") (class "Default")
      (node (ref "X1") (pin "C10") (pinfunction "B_C10") (pintype "passive"))
    )
    (net (code "77") (name "Net-(IC1A-A1)") (class "Default")
      (node (ref "0000") (pin "8") (pinfunction "8_8") (pintype "passive"))
      (node (ref "IC1") (pin "2") (pinfunction "A1_2") (pintype "input"))
      (node (ref "RN1") (pin "9") (pinfunction "9_9") (pintype "passive"))
    )
    (net (code "78") (name "Net-(IC1A-A2)") (class "Default")
      (node (ref "0000") (pin "7") (pinfunction "7_7") (pintype "passive"))
      (node (ref "IC1") (pin "4") (pinfunction "A2_4") (pintype "input"))
      (node (ref "RN1") (pin "8") (pinfunction "8_8") (pintype "passive"))
    )
    (net (code "79") (name "Net-(IC1A-A3)") (class "Default")
      (node (ref "0000") (pin "6") (pinfunction "6_6") (pintype "passive"))
      (node (ref "IC1") (pin "6") (pinfunction "A3_6") (pintype "input"))
      (node (ref "RN1") (pin "7") (pinfunction "7_7") (pintype "passive"))
    )
    (net (code "80") (name "Net-(IC1A-A4)") (class "Default")
      (node (ref "0000") (pin "5") (pinfunction "5_5") (pintype "passive"))
      (node (ref "IC1") (pin "8") (pinfunction "A4_8") (pintype "input"))
      (node (ref "RN1") (pin "6") (pinfunction "6_6") (pintype "passive"))
    )
    (net (code "81") (name "Net-(IC1B-A1)") (class "Default")
      (node (ref "0000") (pin "4") (pinfunction "4_4") (pintype "passive"))
      (node (ref "IC1") (pin "11") (pinfunction "A1_11") (pintype "input"))
      (node (ref "RN1") (pin "5") (pinfunction "5_5") (pintype "passive"))
    )
    (net (code "82") (name "Net-(IC1B-A2)") (class "Default")
      (node (ref "0000") (pin "3") (pinfunction "3_3") (pintype "passive"))
      (node (ref "IC1") (pin "13") (pinfunction "A2_13") (pintype "input"))
      (node (ref "RN1") (pin "4") (pinfunction "4_4") (pintype "passive"))
    )
    (net (code "83") (name "Net-(IC1B-A3)") (class "Default")
      (node (ref "0000") (pin "2") (pinfunction "2_2") (pintype "passive"))
      (node (ref "IC1") (pin "15") (pinfunction "A3_15") (pintype "input"))
      (node (ref "RN1") (pin "3") (pinfunction "3_3") (pintype "passive"))
    )
    (net (code "84") (name "Net-(IC1B-A4)") (class "Default")
      (node (ref "0000") (pin "1") (pinfunction "1_1") (pintype "passive"))
      (node (ref "IC1") (pin "17") (pinfunction "A4_17") (pintype "input"))
      (node (ref "RN1") (pin "2") (pinfunction "2_2") (pintype "passive"))
    )
    (net (code "85") (name "Net-(IC2A-A1)") (class "Default")
      (node (ref "0001") (pin "8") (pinfunction "8_8") (pintype "passive"))
      (node (ref "IC2") (pin "2") (pinfunction "A1_2") (pintype "input"))
      (node (ref "RN2") (pin "9") (pinfunction "9_9") (pintype "passive"))
    )
    (net (code "86") (name "Net-(IC2A-A2)") (class "Default")
      (node (ref "0001") (pin "7") (pinfunction "7_7") (pintype "passive"))
      (node (ref "IC2") (pin "4") (pinfunction "A2_4") (pintype "input"))
      (node (ref "RN2") (pin "8") (pinfunction "8_8") (pintype "passive"))
    )
    (net (code "87") (name "Net-(IC2A-A3)") (class "Default")
      (node (ref "0001") (pin "6") (pinfunction "6_6") (pintype "passive"))
      (node (ref "IC2") (pin "6") (pinfunction "A3_6") (pintype "input"))
      (node (ref "RN2") (pin "7") (pinfunction "7_7") (pintype "passive"))
    )
    (net (code "88") (name "Net-(IC2A-A4)") (class "Default")
      (node (ref "0001") (pin "5") (pinfunction "5_5") (pintype "passive"))
      (node (ref "IC2") (pin "8") (pinfunction "A4_8") (pintype "input"))
      (node (ref "RN2") (pin "6") (pinfunction "6_6") (pintype "passive"))
    )
    (net (code "89") (name "Net-(IC2B-A1)") (class "Default")
      (node (ref "0001") (pin "4") (pinfunction "4_4") (pintype "passive"))
      (node (ref "IC2") (pin "11") (pinfunction "A1_11") (pintype "input"))
      (node (ref "RN2") (pin "5") (pinfunction "5_5") (pintype "passive"))
    )
    (net (code "90") (name "Net-(IC2B-A2)") (class "Default")
      (node (ref "0001") (pin "3") (pinfunction "3_3") (pintype "passive"))
      (node (ref "IC2") (pin "13") (pinfunction "A2_13") (pintype "input"))
      (node (ref "RN2") (pin "4") (pinfunction "4_4") (pintype "passive"))
    )
    (net (code "91") (name "Net-(IC2B-A3)") (class "Default")
      (node (ref "0001") (pin "2") (pinfunction "2_2") (pintype "passive"))
      (node (ref "IC2") (pin "15") (pinfunction "A3_15") (pintype "input"))
      (node (ref "RN2") (pin "3") (pinfunction "3_3") (pintype "passive"))
    )
    (net (code "92") (name "Net-(IC2B-A4)") (class "Default")
      (node (ref "0001") (pin "1") (pinfunction "1_1") (pintype "passive"))
      (node (ref "IC2") (pin "17") (pinfunction "A4_17") (pintype "input"))
      (node (ref "RN2") (pin "2") (pinfunction "2_2") (pintype "passive"))
    )
    (net (code "93") (name "Net-(IC3A-A1)") (class "Default")
      (node (ref "0010") (pin "8") (pinfunction "8_8") (pintype "passive"))
      (node (ref "IC3") (pin "2") (pinfunction "A1_2") (pintype "input"))
      (node (ref "RN3") (pin "9") (pinfunction "9_9") (pintype "passive"))
    )
    (net (code "94") (name "Net-(IC3A-A2)") (class "Default")
      (node (ref "0010") (pin "7") (pinfunction "7_7") (pintype "passive"))
      (node (ref "IC3") (pin "4") (pinfunction "A2_4") (pintype "input"))
      (node (ref "RN3") (pin "8") (pinfunction "8_8") (pintype "passive"))
    )
    (net (code "95") (name "Net-(IC3A-A3)") (class "Default")
      (node (ref "0010") (pin "6") (pinfunction "6_6") (pintype "passive"))
      (node (ref "IC3") (pin "6") (pinfunction "A3_6") (pintype "input"))
      (node (ref "RN3") (pin "7") (pinfunction "7_7") (pintype "passive"))
    )
    (net (code "96") (name "Net-(IC3A-A4)") (class "Default")
      (node (ref "0010") (pin "5") (pinfunction "5_5") (pintype "passive"))
      (node (ref "IC3") (pin "8") (pinfunction "A4_8") (pintype "input"))
      (node (ref "RN3") (pin "6") (pinfunction "6_6") (pintype "passive"))
    )
    (net (code "97") (name "Net-(IC3B-A1)") (class "Default")
      (node (ref "0010") (pin "4") (pinfunction "4_4") (pintype "passive"))
      (node (ref "IC3") (pin "11") (pinfunction "A1_11") (pintype "input"))
      (node (ref "RN3") (pin "5") (pinfunction "5_5") (pintype "passive"))
    )
    (net (code "98") (name "Net-(IC3B-A2)") (class "Default")
      (node (ref "0010") (pin "3") (pinfunction "3_3") (pintype "passive"))
      (node (ref "IC3") (pin "13") (pinfunction "A2_13") (pintype "input"))
      (node (ref "RN3") (pin "4") (pinfunction "4_4") (pintype "passive"))
    )
    (net (code "99") (name "Net-(IC3B-A3)") (class "Default")
      (node (ref "0010") (pin "2") (pinfunction "2_2") (pintype "passive"))
      (node (ref "IC3") (pin "15") (pinfunction "A3_15") (pintype "input"))
      (node (ref "RN3") (pin "3") (pinfunction "3_3") (pintype "passive"))
    )
    (net (code "100") (name "Net-(IC3B-A4)") (class "Default")
      (node (ref "0010") (pin "1") (pinfunction "1_1") (pintype "passive"))
      (node (ref "IC3") (pin "17") (pinfunction "A4_17") (pintype "input"))
      (node (ref "RN3") (pin "2") (pinfunction "2_2") (pintype "passive"))
    )
    (net (code "101") (name "Net-(IC4A-A1)") (class "Default")
      (node (ref "0011") (pin "8") (pinfunction "8_8") (pintype "passive"))
      (node (ref "IC4") (pin "2") (pinfunction "A1_2") (pintype "input"))
      (node (ref "RN4") (pin "9") (pinfunction "9_9") (pintype "passive"))
    )
    (net (code "102") (name "Net-(IC4A-A2)") (class "Default")
      (node (ref "0011") (pin "7") (pinfunction "7_7") (pintype "passive"))
      (node (ref "IC4") (pin "4") (pinfunction "A2_4") (pintype "input"))
      (node (ref "RN4") (pin "8") (pinfunction "8_8") (pintype "passive"))
    )
    (net (code "103") (name "Net-(IC4A-A3)") (class "Default")
      (node (ref "0011") (pin "6") (pinfunction "6_6") (pintype "passive"))
      (node (ref "IC4") (pin "6") (pinfunction "A3_6") (pintype "input"))
      (node (ref "RN4") (pin "7") (pinfunction "7_7") (pintype "passive"))
    )
    (net (code "104") (name "Net-(IC4A-A4)") (class "Default")
      (node (ref "0011") (pin "5") (pinfunction "5_5") (pintype "passive"))
      (node (ref "IC4") (pin "8") (pinfunction "A4_8") (pintype "input"))
      (node (ref "RN4") (pin "6") (pinfunction "6_6") (pintype "passive"))
    )
    (net (code "105") (name "Net-(IC4B-A1)") (class "Default")
      (node (ref "0011") (pin "4") (pinfunction "4_4") (pintype "passive"))
      (node (ref "IC4") (pin "11") (pinfunction "A1_11") (pintype "input"))
      (node (ref "RN4") (pin "5") (pinfunction "5_5") (pintype "passive"))
    )
    (net (code "106") (name "Net-(IC4B-A2)") (class "Default")
      (node (ref "0011") (pin "3") (pinfunction "3_3") (pintype "passive"))
      (node (ref "IC4") (pin "13") (pinfunction "A2_13") (pintype "input"))
      (node (ref "RN4") (pin "4") (pinfunction "4_4") (pintype "passive"))
    )
    (net (code "107") (name "Net-(IC4B-A3)") (class "Default")
      (node (ref "0011") (pin "2") (pinfunction "2_2") (pintype "passive"))
      (node (ref "IC4") (pin "15") (pinfunction "A3_15") (pintype "input"))
      (node (ref "RN4") (pin "3") (pinfunction "3_3") (pintype "passive"))
    )
    (net (code "108") (name "Net-(IC4B-A4)") (class "Default")
      (node (ref "0011") (pin "1") (pinfunction "1_1") (pintype "passive"))
      (node (ref "IC4") (pin "17") (pinfunction "A4_17") (pintype "input"))
      (node (ref "RN4") (pin "2") (pinfunction "2_2") (pintype "passive"))
    )
    (net (code "109") (name "Net-(IC5A-A1)") (class "Default")
      (node (ref "0100") (pin "8") (pinfunction "8_8") (pintype "passive"))
      (node (ref "IC5") (pin "2") (pinfunction "A1_2") (pintype "input"))
      (node (ref "RN5") (pin "9") (pinfunction "9_9") (pintype "passive"))
    )
    (net (code "110") (name "Net-(IC5A-A2)") (class "Default")
      (node (ref "0100") (pin "7") (pinfunction "7_7") (pintype "passive"))
      (node (ref "IC5") (pin "4") (pinfunction "A2_4") (pintype "input"))
      (node (ref "RN5") (pin "8") (pinfunction "8_8") (pintype "passive"))
    )
    (net (code "111") (name "Net-(IC5A-A3)") (class "Default")
      (node (ref "0100") (pin "6") (pinfunction "6_6") (pintype "passive"))
      (node (ref "IC5") (pin "6") (pinfunction "A3_6") (pintype "input"))
      (node (ref "RN5") (pin "7") (pinfunction "7_7") (pintype "passive"))
    )
    (net (code "112") (name "Net-(IC5A-A4)") (class "Default")
      (node (ref "0100") (pin "5") (pinfunction "5_5") (pintype "passive"))
      (node (ref "IC5") (pin "8") (pinfunction "A4_8") (pintype "input"))
      (node (ref "RN5") (pin "6") (pinfunction "6_6") (pintype "passive"))
    )
    (net (code "113") (name "Net-(IC5B-A1)") (class "Default")
      (node (ref "0100") (pin "4") (pinfunction "4_4") (pintype "passive"))
      (node (ref "IC5") (pin "11") (pinfunction "A1_11") (pintype "input"))
      (node (ref "RN5") (pin "5") (pinfunction "5_5") (pintype "passive"))
    )
    (net (code "114") (name "Net-(IC5B-A2)") (class "Default")
      (node (ref "0100") (pin "3") (pinfunction "3_3") (pintype "passive"))
      (node (ref "IC5") (pin "13") (pinfunction "A2_13") (pintype "input"))
      (node (ref "RN5") (pin "4") (pinfunction "4_4") (pintype "passive"))
    )
    (net (code "115") (name "Net-(IC5B-A3)") (class "Default")
      (node (ref "0100") (pin "2") (pinfunction "2_2") (pintype "passive"))
      (node (ref "IC5") (pin "15") (pinfunction "A3_15") (pintype "input"))
      (node (ref "RN5") (pin "3") (pinfunction "3_3") (pintype "passive"))
    )
    (net (code "116") (name "Net-(IC5B-A4)") (class "Default")
      (node (ref "0100") (pin "1") (pinfunction "1_1") (pintype "passive"))
      (node (ref "IC5") (pin "17") (pinfunction "A4_17") (pintype "input"))
      (node (ref "RN5") (pin "2") (pinfunction "2_2") (pintype "passive"))
    )
    (net (code "117") (name "Net-(IC6A-A1)") (class "Default")
      (node (ref "0101") (pin "8") (pinfunction "8_8") (pintype "passive"))
      (node (ref "IC6") (pin "2") (pinfunction "A1_2") (pintype "input"))
      (node (ref "RN6") (pin "9") (pinfunction "9_9") (pintype "passive"))
    )
    (net (code "118") (name "Net-(IC6A-A2)") (class "Default")
      (node (ref "0101") (pin "7") (pinfunction "7_7") (pintype "passive"))
      (node (ref "IC6") (pin "4") (pinfunction "A2_4") (pintype "input"))
      (node (ref "RN6") (pin "8") (pinfunction "8_8") (pintype "passive"))
    )
    (net (code "119") (name "Net-(IC6A-A3)") (class "Default")
      (node (ref "0101") (pin "6") (pinfunction "6_6") (pintype "passive"))
      (node (ref "IC6") (pin "6") (pinfunction "A3_6") (pintype "input"))
      (node (ref "RN6") (pin "7") (pinfunction "7_7") (pintype "passive"))
    )
    (net (code "120") (name "Net-(IC6A-A4)") (class "Default")
      (node (ref "0101") (pin "5") (pinfunction "5_5") (pintype "passive"))
      (node (ref "IC6") (pin "8") (pinfunction "A4_8") (pintype "input"))
      (node (ref "RN6") (pin "6") (pinfunction "6_6") (pintype "passive"))
    )
    (net (code "121") (name "Net-(IC6B-A1)") (class "Default")
      (node (ref "0101") (pin "4") (pinfunction "4_4") (pintype "passive"))
      (node (ref "IC6") (pin "11") (pinfunction "A1_11") (pintype "input"))
      (node (ref "RN6") (pin "5") (pinfunction "5_5") (pintype "passive"))
    )
    (net (code "122") (name "Net-(IC6B-A2)") (class "Default")
      (node (ref "0101") (pin "3") (pinfunction "3_3") (pintype "passive"))
      (node (ref "IC6") (pin "13") (pinfunction "A2_13") (pintype "input"))
      (node (ref "RN6") (pin "4") (pinfunction "4_4") (pintype "passive"))
    )
    (net (code "123") (name "Net-(IC6B-A3)") (class "Default")
      (node (ref "0101") (pin "2") (pinfunction "2_2") (pintype "passive"))
      (node (ref "IC6") (pin "15") (pinfunction "A3_15") (pintype "input"))
      (node (ref "RN6") (pin "3") (pinfunction "3_3") (pintype "passive"))
    )
    (net (code "124") (name "Net-(IC6B-A4)") (class "Default")
      (node (ref "0101") (pin "1") (pinfunction "1_1") (pintype "passive"))
      (node (ref "IC6") (pin "17") (pinfunction "A4_17") (pintype "input"))
      (node (ref "RN6") (pin "2") (pinfunction "2_2") (pintype "passive"))
    )
    (net (code "125") (name "Net-(IC7A-A1)") (class "Default")
      (node (ref "0110") (pin "8") (pinfunction "8_8") (pintype "passive"))
      (node (ref "IC7") (pin "2") (pinfunction "A1_2") (pintype "input"))
      (node (ref "RN7") (pin "9") (pinfunction "9_9") (pintype "passive"))
    )
    (net (code "126") (name "Net-(IC7A-A2)") (class "Default")
      (node (ref "0110") (pin "7") (pinfunction "7_7") (pintype "passive"))
      (node (ref "IC7") (pin "4") (pinfunction "A2_4") (pintype "input"))
      (node (ref "RN7") (pin "8") (pinfunction "8_8") (pintype "passive"))
    )
    (net (code "127") (name "Net-(IC7A-A3)") (class "Default")
      (node (ref "0110") (pin "6") (pinfunction "6_6") (pintype "passive"))
      (node (ref "IC7") (pin "6") (pinfunction "A3_6") (pintype "input"))
      (node (ref "RN7") (pin "7") (pinfunction "7_7") (pintype "passive"))
    )
    (net (code "128") (name "Net-(IC7A-A4)") (class "Default")
      (node (ref "0110") (pin "5") (pinfunction "5_5") (pintype "passive"))
      (node (ref "IC7") (pin "8") (pinfunction "A4_8") (pintype "input"))
      (node (ref "RN7") (pin "6") (pinfunction "6_6") (pintype "passive"))
    )
    (net (code "129") (name "Net-(IC7B-A1)") (class "Default")
      (node (ref "0110") (pin "4") (pinfunction "4_4") (pintype "passive"))
      (node (ref "IC7") (pin "11") (pinfunction "A1_11") (pintype "input"))
      (node (ref "RN7") (pin "5") (pinfunction "5_5") (pintype "passive"))
    )
    (net (code "130") (name "Net-(IC7B-A2)") (class "Default")
      (node (ref "0110") (pin "3") (pinfunction "3_3") (pintype "passive"))
      (node (ref "IC7") (pin "13") (pinfunction "A2_13") (pintype "input"))
      (node (ref "RN7") (pin "4") (pinfunction "4_4") (pintype "passive"))
    )
    (net (code "131") (name "Net-(IC7B-A3)") (class "Default")
      (node (ref "0110") (pin "2") (pinfunction "2_2") (pintype "passive"))
      (node (ref "IC7") (pin "15") (pinfunction "A3_15") (pintype "input"))
      (node (ref "RN7") (pin "3") (pinfunction "3_3") (pintype "passive"))
    )
    (net (code "132") (name "Net-(IC7B-A4)") (class "Default")
      (node (ref "0110") (pin "1") (pinfunction "1_1") (pintype "passive"))
      (node (ref "IC7") (pin "17") (pinfunction "A4_17") (pintype "input"))
      (node (ref "RN7") (pin "2") (pinfunction "2_2") (pintype "passive"))
    )
    (net (code "133") (name "Net-(IC8A-A1)") (class "Default")
      (node (ref "0111") (pin "8") (pinfunction "8_8") (pintype "passive"))
      (node (ref "IC8") (pin "2") (pinfunction "A1_2") (pintype "input"))
      (node (ref "RN8") (pin "9") (pinfunction "9_9") (pintype "passive"))
    )
    (net (code "134") (name "Net-(IC8A-A2)") (class "Default")
      (node (ref "0111") (pin "7") (pinfunction "7_7") (pintype "passive"))
      (node (ref "IC8") (pin "4") (pinfunction "A2_4") (pintype "input"))
      (node (ref "RN8") (pin "8") (pinfunction "8_8") (pintype "passive"))
    )
    (net (code "135") (name "Net-(IC8A-A3)") (class "Default")
      (node (ref "0111") (pin "6") (pinfunction "6_6") (pintype "passive"))
      (node (ref "IC8") (pin "6") (pinfunction "A3_6") (pintype "input"))
      (node (ref "RN8") (pin "7") (pinfunction "7_7") (pintype "passive"))
    )
    (net (code "136") (name "Net-(IC8A-A4)") (class "Default")
      (node (ref "0111") (pin "5") (pinfunction "5_5") (pintype "passive"))
      (node (ref "IC8") (pin "8") (pinfunction "A4_8") (pintype "input"))
      (node (ref "RN8") (pin "6") (pinfunction "6_6") (pintype "passive"))
    )
    (net (code "137") (name "Net-(IC8B-A1)") (class "Default")
      (node (ref "0111") (pin "4") (pinfunction "4_4") (pintype "passive"))
      (node (ref "IC8") (pin "11") (pinfunction "A1_11") (pintype "input"))
      (node (ref "RN8") (pin "5") (pinfunction "5_5") (pintype "passive"))
    )
    (net (code "138") (name "Net-(IC8B-A2)") (class "Default")
      (node (ref "0111") (pin "3") (pinfunction "3_3") (pintype "passive"))
      (node (ref "IC8") (pin "13") (pinfunction "A2_13") (pintype "input"))
      (node (ref "RN8") (pin "4") (pinfunction "4_4") (pintype "passive"))
    )
    (net (code "139") (name "Net-(IC8B-A3)") (class "Default")
      (node (ref "0111") (pin "2") (pinfunction "2_2") (pintype "passive"))
      (node (ref "IC8") (pin "15") (pinfunction "A3_15") (pintype "input"))
      (node (ref "RN8") (pin "3") (pinfunction "3_3") (pintype "passive"))
    )
    (net (code "140") (name "Net-(IC8B-A4)") (class "Default")
      (node (ref "0111") (pin "1") (pinfunction "1_1") (pintype "passive"))
      (node (ref "IC8") (pin "17") (pinfunction "A4_17") (pintype "input"))
      (node (ref "RN8") (pin "2") (pinfunction "2_2") (pintype "passive"))
    )
    (net (code "141") (name "Net-(IC9A-A1)") (class "Default")
      (node (ref "1000") (pin "8") (pinfunction "8_8") (pintype "passive"))
      (node (ref "IC9") (pin "2") (pinfunction "A1_2") (pintype "input"))
      (node (ref "RN9") (pin "9") (pinfunction "9_9") (pintype "passive"))
    )
    (net (code "142") (name "Net-(IC9A-A2)") (class "Default")
      (node (ref "1000") (pin "7") (pinfunction "7_7") (pintype "passive"))
      (node (ref "IC9") (pin "4") (pinfunction "A2_4") (pintype "input"))
      (node (ref "RN9") (pin "8") (pinfunction "8_8") (pintype "passive"))
    )
    (net (code "143") (name "Net-(IC9A-A3)") (class "Default")
      (node (ref "1000") (pin "6") (pinfunction "6_6") (pintype "passive"))
      (node (ref "IC9") (pin "6") (pinfunction "A3_6") (pintype "input"))
      (node (ref "RN9") (pin "7") (pinfunction "7_7") (pintype "passive"))
    )
    (net (code "144") (name "Net-(IC9A-A4)") (class "Default")
      (node (ref "1000") (pin "5") (pinfunction "5_5") (pintype "passive"))
      (node (ref "IC9") (pin "8") (pinfunction "A4_8") (pintype "input"))
      (node (ref "RN9") (pin "6") (pinfunction "6_6") (pintype "passive"))
    )
    (net (code "145") (name "Net-(IC9B-A1)") (class "Default")
      (node (ref "1000") (pin "4") (pinfunction "4_4") (pintype "passive"))
      (node (ref "IC9") (pin "11") (pinfunction "A1_11") (pintype "input"))
      (node (ref "RN9") (pin "5") (pinfunction "5_5") (pintype "passive"))
    )
    (net (code "146") (name "Net-(IC9B-A2)") (class "Default")
      (node (ref "1000") (pin "3") (pinfunction "3_3") (pintype "passive"))
      (node (ref "IC9") (pin "13") (pinfunction "A2_13") (pintype "input"))
      (node (ref "RN9") (pin "4") (pinfunction "4_4") (pintype "passive"))
    )
    (net (code "147") (name "Net-(IC9B-A3)") (class "Default")
      (node (ref "1000") (pin "2") (pinfunction "2_2") (pintype "passive"))
      (node (ref "IC9") (pin "15") (pinfunction "A3_15") (pintype "input"))
      (node (ref "RN9") (pin "3") (pinfunction "3_3") (pintype "passive"))
    )
    (net (code "148") (name "Net-(IC9B-A4)") (class "Default")
      (node (ref "1000") (pin "1") (pinfunction "1_1") (pintype "passive"))
      (node (ref "IC9") (pin "17") (pinfunction "A4_17") (pintype "input"))
      (node (ref "RN9") (pin "2") (pinfunction "2_2") (pintype "passive"))
    )
    (net (code "149") (name "Net-(IC10A-A1)") (class "Default")
      (node (ref "1001") (pin "8") (pinfunction "8_8") (pintype "passive"))
      (node (ref "IC10") (pin "2") (pinfunction "A1_2") (pintype "input"))
      (node (ref "RN10") (pin "9") (pinfunction "9_9") (pintype "passive"))
    )
    (net (code "150") (name "Net-(IC10A-A2)") (class "Default")
      (node (ref "1001") (pin "7") (pinfunction "7_7") (pintype "passive"))
      (node (ref "IC10") (pin "4") (pinfunction "A2_4") (pintype "input"))
      (node (ref "RN10") (pin "8") (pinfunction "8_8") (pintype "passive"))
    )
    (net (code "151") (name "Net-(IC10A-A3)") (class "Default")
      (node (ref "1001") (pin "6") (pinfunction "6_6") (pintype "passive"))
      (node (ref "IC10") (pin "6") (pinfunction "A3_6") (pintype "input"))
      (node (ref "RN10") (pin "7") (pinfunction "7_7") (pintype "passive"))
    )
    (net (code "152") (name "Net-(IC10A-A4)") (class "Default")
      (node (ref "1001") (pin "5") (pinfunction "5_5") (pintype "passive"))
      (node (ref "IC10") (pin "8") (pinfunction "A4_8") (pintype "input"))
      (node (ref "RN10") (pin "6") (pinfunction "6_6") (pintype "passive"))
    )
    (net (code "153") (name "Net-(IC10B-A1)") (class "Default")
      (node (ref "1001") (pin "4") (pinfunction "4_4") (pintype "passive"))
      (node (ref "IC10") (pin "11") (pinfunction "A1_11") (pintype "input"))
      (node (ref "RN10") (pin "5") (pinfunction "5_5") (pintype "passive"))
    )
    (net (code "154") (name "Net-(IC10B-A2)") (class "Default")
      (node (ref "1001") (pin "3") (pinfunction "3_3") (pintype "passive"))
      (node (ref "IC10") (pin "13") (pinfunction "A2_13") (pintype "input"))
      (node (ref "RN10") (pin "4") (pinfunction "4_4") (pintype "passive"))
    )
    (net (code "155") (name "Net-(IC10B-A3)") (class "Default")
      (node (ref "1001") (pin "2") (pinfunction "2_2") (pintype "passive"))
      (node (ref "IC10") (pin "15") (pinfunction "A3_15") (pintype "input"))
      (node (ref "RN10") (pin "3") (pinfunction "3_3") (pintype "passive"))
    )
    (net (code "156") (name "Net-(IC10B-A4)") (class "Default")
      (node (ref "1001") (pin "1") (pinfunction "1_1") (pintype "passive"))
      (node (ref "IC10") (pin "17") (pinfunction "A4_17") (pintype "input"))
      (node (ref "RN10") (pin "2") (pinfunction "2_2") (pintype "passive"))
    )
    (net (code "157") (name "Net-(IC11A-A1)") (class "Default")
      (node (ref "1010") (pin "8") (pinfunction "8_8") (pintype "passive"))
      (node (ref "IC11") (pin "2") (pinfunction "A1_2") (pintype "input"))
      (node (ref "RN11") (pin "9") (pinfunction "9_9") (pintype "passive"))
    )
    (net (code "158") (name "Net-(IC11A-A2)") (class "Default")
      (node (ref "1010") (pin "7") (pinfunction "7_7") (pintype "passive"))
      (node (ref "IC11") (pin "4") (pinfunction "A2_4") (pintype "input"))
      (node (ref "RN11") (pin "8") (pinfunction "8_8") (pintype "passive"))
    )
    (net (code "159") (name "Net-(IC11A-A3)") (class "Default")
      (node (ref "1010") (pin "6") (pinfunction "6_6") (pintype "passive"))
      (node (ref "IC11") (pin "6") (pinfunction "A3_6") (pintype "input"))
      (node (ref "RN11") (pin "7") (pinfunction "7_7") (pintype "passive"))
    )
    (net (code "160") (name "Net-(IC11A-A4)") (class "Default")
      (node (ref "1010") (pin "5") (pinfunction "5_5") (pintype "passive"))
      (node (ref "IC11") (pin "8") (pinfunction "A4_8") (pintype "input"))
      (node (ref "RN11") (pin "6") (pinfunction "6_6") (pintype "passive"))
    )
    (net (code "161") (name "Net-(IC11B-A1)") (class "Default")
      (node (ref "1010") (pin "4") (pinfunction "4_4") (pintype "passive"))
      (node (ref "IC11") (pin "11") (pinfunction "A1_11") (pintype "input"))
      (node (ref "RN11") (pin "5") (pinfunction "5_5") (pintype "passive"))
    )
    (net (code "162") (name "Net-(IC11B-A2)") (class "Default")
      (node (ref "1010") (pin "3") (pinfunction "3_3") (pintype "passive"))
      (node (ref "IC11") (pin "13") (pinfunction "A2_13") (pintype "input"))
      (node (ref "RN11") (pin "4") (pinfunction "4_4") (pintype "passive"))
    )
    (net (code "163") (name "Net-(IC11B-A3)") (class "Default")
      (node (ref "1010") (pin "2") (pinfunction "2_2") (pintype "passive"))
      (node (ref "IC11") (pin "15") (pinfunction "A3_15") (pintype "input"))
      (node (ref "RN11") (pin "3") (pinfunction "3_3") (pintype "passive"))
    )
    (net (code "164") (name "Net-(IC11B-A4)") (class "Default")
      (node (ref "1010") (pin "1") (pinfunction "1_1") (pintype "passive"))
      (node (ref "IC11") (pin "17") (pinfunction "A4_17") (pintype "input"))
      (node (ref "RN11") (pin "2") (pinfunction "2_2") (pintype "passive"))
    )
    (net (code "165") (name "Net-(IC12A-A1)") (class "Default")
      (node (ref "1011") (pin "8") (pinfunction "8_8") (pintype "passive"))
      (node (ref "IC12") (pin "2") (pinfunction "A1_2") (pintype "input"))
      (node (ref "RN12") (pin "9") (pinfunction "9_9") (pintype "passive"))
    )
    (net (code "166") (name "Net-(IC12A-A2)") (class "Default")
      (node (ref "1011") (pin "7") (pinfunction "7_7") (pintype "passive"))
      (node (ref "IC12") (pin "4") (pinfunction "A2_4") (pintype "input"))
      (node (ref "RN12") (pin "8") (pinfunction "8_8") (pintype "passive"))
    )
    (net (code "167") (name "Net-(IC12A-A3)") (class "Default")
      (node (ref "1011") (pin "6") (pinfunction "6_6") (pintype "passive"))
      (node (ref "IC12") (pin "6") (pinfunction "A3_6") (pintype "input"))
      (node (ref "RN12") (pin "7") (pinfunction "7_7") (pintype "passive"))
    )
    (net (code "168") (name "Net-(IC12A-A4)") (class "Default")
      (node (ref "1011") (pin "5") (pinfunction "5_5") (pintype "passive"))
      (node (ref "IC12") (pin "8") (pinfunction "A4_8") (pintype "input"))
      (node (ref "RN12") (pin "6") (pinfunction "6_6") (pintype "passive"))
    )
    (net (code "169") (name "Net-(IC12B-A1)") (class "Default")
      (node (ref "1011") (pin "4") (pinfunction "4_4") (pintype "passive"))
      (node (ref "IC12") (pin "11") (pinfunction "A1_11") (pintype "input"))
      (node (ref "RN12") (pin "5") (pinfunction "5_5") (pintype "passive"))
    )
    (net (code "170") (name "Net-(IC12B-A2)") (class "Default")
      (node (ref "1011") (pin "3") (pinfunction "3_3") (pintype "passive"))
      (node (ref "IC12") (pin "13") (pinfunction "A2_13") (pintype "input"))
      (node (ref "RN12") (pin "4") (pinfunction "4_4") (pintype "passive"))
    )
    (net (code "171") (name "Net-(IC12B-A3)") (class "Default")
      (node (ref "1011") (pin "2") (pinfunction "2_2") (pintype "passive"))
      (node (ref "IC12") (pin "15") (pinfunction "A3_15") (pintype "input"))
      (node (ref "RN12") (pin "3") (pinfunction "3_3") (pintype "passive"))
    )
    (net (code "172") (name "Net-(IC12B-A4)") (class "Default")
      (node (ref "1011") (pin "1") (pinfunction "1_1") (pintype "passive"))
      (node (ref "IC12") (pin "17") (pinfunction "A4_17") (pintype "input"))
      (node (ref "RN12") (pin "2") (pinfunction "2_2") (pintype "passive"))
    )
    (net (code "173") (name "Net-(IC13A-A1)") (class "Default")
      (node (ref "1100") (pin "8") (pinfunction "8_8") (pintype "passive"))
      (node (ref "IC13") (pin "2") (pinfunction "A1_2") (pintype "input"))
      (node (ref "RN13") (pin "9") (pinfunction "9_9") (pintype "passive"))
    )
    (net (code "174") (name "Net-(IC13A-A2)") (class "Default")
      (node (ref "1100") (pin "7") (pinfunction "7_7") (pintype "passive"))
      (node (ref "IC13") (pin "4") (pinfunction "A2_4") (pintype "input"))
      (node (ref "RN13") (pin "8") (pinfunction "8_8") (pintype "passive"))
    )
    (net (code "175") (name "Net-(IC13A-A3)") (class "Default")
      (node (ref "1100") (pin "6") (pinfunction "6_6") (pintype "passive"))
      (node (ref "IC13") (pin "6") (pinfunction "A3_6") (pintype "input"))
      (node (ref "RN13") (pin "7") (pinfunction "7_7") (pintype "passive"))
    )
    (net (code "176") (name "Net-(IC13A-A4)") (class "Default")
      (node (ref "1100") (pin "5") (pinfunction "5_5") (pintype "passive"))
      (node (ref "IC13") (pin "8") (pinfunction "A4_8") (pintype "input"))
      (node (ref "RN13") (pin "6") (pinfunction "6_6") (pintype "passive"))
    )
    (net (code "177") (name "Net-(IC13B-A1)") (class "Default")
      (node (ref "1100") (pin "4") (pinfunction "4_4") (pintype "passive"))
      (node (ref "IC13") (pin "11") (pinfunction "A1_11") (pintype "input"))
      (node (ref "RN13") (pin "5") (pinfunction "5_5") (pintype "passive"))
    )
    (net (code "178") (name "Net-(IC13B-A2)") (class "Default")
      (node (ref "1100") (pin "3") (pinfunction "3_3") (pintype "passive"))
      (node (ref "IC13") (pin "13") (pinfunction "A2_13") (pintype "input"))
      (node (ref "RN13") (pin "4") (pinfunction "4_4") (pintype "passive"))
    )
    (net (code "179") (name "Net-(IC13B-A3)") (class "Default")
      (node (ref "1100") (pin "2") (pinfunction "2_2") (pintype "passive"))
      (node (ref "IC13") (pin "15") (pinfunction "A3_15") (pintype "input"))
      (node (ref "RN13") (pin "3") (pinfunction "3_3") (pintype "passive"))
    )
    (net (code "180") (name "Net-(IC13B-A4)") (class "Default")
      (node (ref "1100") (pin "1") (pinfunction "1_1") (pintype "passive"))
      (node (ref "IC13") (pin "17") (pinfunction "A4_17") (pintype "input"))
      (node (ref "RN13") (pin "2") (pinfunction "2_2") (pintype "passive"))
    )
    (net (code "181") (name "Net-(IC14A-A1)") (class "Default")
      (node (ref "1101") (pin "8") (pinfunction "8_8") (pintype "passive"))
      (node (ref "IC14") (pin "2") (pinfunction "A1_2") (pintype "input"))
      (node (ref "RN14") (pin "9") (pinfunction "9_9") (pintype "passive"))
    )
    (net (code "182") (name "Net-(IC14A-A2)") (class "Default")
      (node (ref "1101") (pin "7") (pinfunction "7_7") (pintype "passive"))
      (node (ref "IC14") (pin "4") (pinfunction "A2_4") (pintype "input"))
      (node (ref "RN14") (pin "8") (pinfunction "8_8") (pintype "passive"))
    )
    (net (code "183") (name "Net-(IC14A-A3)") (class "Default")
      (node (ref "1101") (pin "6") (pinfunction "6_6") (pintype "passive"))
      (node (ref "IC14") (pin "6") (pinfunction "A3_6") (pintype "input"))
      (node (ref "RN14") (pin "7") (pinfunction "7_7") (pintype "passive"))
    )
    (net (code "184") (name "Net-(IC14A-A4)") (class "Default")
      (node (ref "1101") (pin "5") (pinfunction "5_5") (pintype "passive"))
      (node (ref "IC14") (pin "8") (pinfunction "A4_8") (pintype "input"))
      (node (ref "RN14") (pin "6") (pinfunction "6_6") (pintype "passive"))
    )
    (net (code "185") (name "Net-(IC14B-A1)") (class "Default")
      (node (ref "1101") (pin "4") (pinfunction "4_4") (pintype "passive"))
      (node (ref "IC14") (pin "11") (pinfunction "A1_11") (pintype "input"))
      (node (ref "RN14") (pin "5") (pinfunction "5_5") (pintype "passive"))
    )
    (net (code "186") (name "Net-(IC14B-A2)") (class "Default")
      (node (ref "1101") (pin "3") (pinfunction "3_3") (pintype "passive"))
      (node (ref "IC14") (pin "13") (pinfunction "A2_13") (pintype "input"))
      (node (ref "RN14") (pin "4") (pinfunction "4_4") (pintype "passive"))
    )
    (net (code "187") (name "Net-(IC14B-A3)") (class "Default")
      (node (ref "1101") (pin "2") (pinfunction "2_2") (pintype "passive"))
      (node (ref "IC14") (pin "15") (pinfunction "A3_15") (pintype "input"))
      (node (ref "RN14") (pin "3") (pinfunction "3_3") (pintype "passive"))
    )
    (net (code "188") (name "Net-(IC14B-A4)") (class "Default")
      (node (ref "1101") (pin "1") (pinfunction "1_1") (pintype "passive"))
      (node (ref "IC14") (pin "17") (pinfunction "A4_17") (pintype "input"))
      (node (ref "RN14") (pin "2") (pinfunction "2_2") (pintype "passive"))
    )
    (net (code "189") (name "Net-(IC15A-A1)") (class "Default")
      (node (ref "1110") (pin "8") (pinfunction "8_8") (pintype "passive"))
      (node (ref "IC15") (pin "2") (pinfunction "A1_2") (pintype "input"))
      (node (ref "RN15") (pin "9") (pinfunction "9_9") (pintype "passive"))
    )
    (net (code "190") (name "Net-(IC15A-A2)") (class "Default")
      (node (ref "1110") (pin "7") (pinfunction "7_7") (pintype "passive"))
      (node (ref "IC15") (pin "4") (pinfunction "A2_4") (pintype "input"))
      (node (ref "RN15") (pin "8") (pinfunction "8_8") (pintype "passive"))
    )
    (net (code "191") (name "Net-(IC15A-A3)") (class "Default")
      (node (ref "1110") (pin "6") (pinfunction "6_6") (pintype "passive"))
      (node (ref "IC15") (pin "6") (pinfunction "A3_6") (pintype "input"))
      (node (ref "RN15") (pin "7") (pinfunction "7_7") (pintype "passive"))
    )
    (net (code "192") (name "Net-(IC15A-A4)") (class "Default")
      (node (ref "1110") (pin "5") (pinfunction "5_5") (pintype "passive"))
      (node (ref "IC15") (pin "8") (pinfunction "A4_8") (pintype "input"))
      (node (ref "RN15") (pin "6") (pinfunction "6_6") (pintype "passive"))
    )
    (net (code "193") (name "Net-(IC15B-A1)") (class "Default")
      (node (ref "1110") (pin "4") (pinfunction "4_4") (pintype "passive"))
      (node (ref "IC15") (pin "11") (pinfunction "A1_11") (pintype "input"))
      (node (ref "RN15") (pin "5") (pinfunction "5_5") (pintype "passive"))
    )
    (net (code "194") (name "Net-(IC15B-A2)") (class "Default")
      (node (ref "1110") (pin "3") (pinfunction "3_3") (pintype "passive"))
      (node (ref "IC15") (pin "13") (pinfunction "A2_13") (pintype "input"))
      (node (ref "RN15") (pin "4") (pinfunction "4_4") (pintype "passive"))
    )
    (net (code "195") (name "Net-(IC15B-A3)") (class "Default")
      (node (ref "1110") (pin "2") (pinfunction "2_2") (pintype "passive"))
      (node (ref "IC15") (pin "15") (pinfunction "A3_15") (pintype "input"))
      (node (ref "RN15") (pin "3") (pinfunction "3_3") (pintype "passive"))
    )
    (net (code "196") (name "Net-(IC15B-A4)") (class "Default")
      (node (ref "1110") (pin "1") (pinfunction "1_1") (pintype "passive"))
      (node (ref "IC15") (pin "17") (pinfunction "A4_17") (pintype "input"))
      (node (ref "RN15") (pin "2") (pinfunction "2_2") (pintype "passive"))
    )
    (net (code "197") (name "Net-(IC16A-A1)") (class "Default")
      (node (ref "1111") (pin "8") (pinfunction "8_8") (pintype "passive"))
      (node (ref "IC16") (pin "2") (pinfunction "A1_2") (pintype "input"))
      (node (ref "RN16") (pin "9") (pinfunction "9_9") (pintype "passive"))
    )
    (net (code "198") (name "Net-(IC16A-A2)") (class "Default")
      (node (ref "1111") (pin "7") (pinfunction "7_7") (pintype "passive"))
      (node (ref "IC16") (pin "4") (pinfunction "A2_4") (pintype "input"))
      (node (ref "RN16") (pin "8") (pinfunction "8_8") (pintype "passive"))
    )
    (net (code "199") (name "Net-(IC16A-A3)") (class "Default")
      (node (ref "1111") (pin "6") (pinfunction "6_6") (pintype "passive"))
      (node (ref "IC16") (pin "6") (pinfunction "A3_6") (pintype "input"))
      (node (ref "RN16") (pin "7") (pinfunction "7_7") (pintype "passive"))
    )
    (net (code "200") (name "Net-(IC16A-A4)") (class "Default")
      (node (ref "1111") (pin "5") (pinfunction "5_5") (pintype "passive"))
      (node (ref "IC16") (pin "8") (pinfunction "A4_8") (pintype "input"))
      (node (ref "RN16") (pin "6") (pinfunction "6_6") (pintype "passive"))
    )
    (net (code "201") (name "Net-(IC16B-A1)") (class "Default")
      (node (ref "1111") (pin "4") (pinfunction "4_4") (pintype "passive"))
      (node (ref "IC16") (pin "11") (pinfunction "A1_11") (pintype "input"))
      (node (ref "RN16") (pin "5") (pinfunction "5_5") (pintype "passive"))
    )
    (net (code "202") (name "Net-(IC16B-A2)") (class "Default")
      (node (ref "1111") (pin "3") (pinfunction "3_3") (pintype "passive"))
      (node (ref "IC16") (pin "13") (pinfunction "A2_13") (pintype "input"))
      (node (ref "RN16") (pin "4") (pinfunction "4_4") (pintype "passive"))
    )
    (net (code "203") (name "Net-(IC16B-A3)") (class "Default")
      (node (ref "1111") (pin "2") (pinfunction "2_2") (pintype "passive"))
      (node (ref "IC16") (pin "15") (pinfunction "A3_15") (pintype "input"))
      (node (ref "RN16") (pin "3") (pinfunction "3_3") (pintype "passive"))
    )
    (net (code "204") (name "Net-(IC16B-A4)") (class "Default")
      (node (ref "1111") (pin "1") (pinfunction "1_1") (pintype "passive"))
      (node (ref "IC16") (pin "17") (pinfunction "A4_17") (pintype "input"))
      (node (ref "RN16") (pin "2") (pinfunction "2_2") (pintype "passive"))
    )
    (net (code "205") (name "Net-(IC17A-G1)") (class "Default")
      (node (ref "IC17") (pin "6") (pinfunction "G1_6") (pintype "input"))
      (node (ref "IC18") (pin "6") (pinfunction "G1_6") (pintype "input"))
      (node (ref "IC21") (pin "6") (pinfunction "G1_6") (pintype "input"))
      (node (ref "V1") (pin "13") (pinfunction "W_13") (pintype "output"))
    )
    (net (code "206") (name "Net-(IC17A-G2B)") (class "Default")
      (node (ref "IC17") (pin "5") (pinfunction "G2B_5") (pintype "input"))
      (node (ref "IC21") (pin "15") (pinfunction "Y0_15") (pintype "output"))
    )
    (net (code "207") (name "Net-(IC18A-G2B)") (class "Default")
      (node (ref "IC18") (pin "5") (pinfunction "G2B_5") (pintype "input"))
      (node (ref "IC21") (pin "14") (pinfunction "Y1_14") (pintype "output"))
    )
    (net (code "208") (name "Net-(PWR-PadA)") (class "Default")
      (node (ref "PWR") (pin "A") (pinfunction "A_A") (pintype "passive"))
      (node (ref "R2") (pin "1") (pinfunction "1_1") (pintype "passive"))
    )
    (net (code "209") (name "OUT") (class "Default")
      (node (ref "X1") (pin "C27") (pinfunction "B_C27") (pintype "passive"))
    )
    (net (code "210") (name "REG-LD-ID0") (class "Default")
      (node (ref "X1") (pin "B13") (pinfunction "B_B13") (pintype "passive"))
    )
    (net (code "211") (name "REG-LD-ID1") (class "Default")
      (node (ref "X1") (pin "B14") (pinfunction "B_B14") (pintype "passive"))
    )
    (net (code "212") (name "REG-LD-ID2") (class "Default")
      (node (ref "X1") (pin "B15") (pinfunction "B_B15") (pintype "passive"))
    )
    (net (code "213") (name "REG-LD-ID3") (class "Default")
      (node (ref "X1") (pin "B16") (pinfunction "B_B16") (pintype "passive"))
    )
    (net (code "214") (name "REG-RD-ID0") (class "Default")
      (node (ref "X1") (pin "B9") (pinfunction "B_B9") (pintype "passive"))
    )
    (net (code "215") (name "REG-RD-ID1") (class "Default")
      (node (ref "X1") (pin "B10") (pinfunction "B_B10") (pintype "passive"))
    )
    (net (code "216") (name "REG-RD-ID2") (class "Default")
      (node (ref "X1") (pin "B11") (pinfunction "B_B11") (pintype "passive"))
    )
    (net (code "217") (name "REG-RD-ID3") (class "Default")
      (node (ref "X1") (pin "B12") (pinfunction "B_B12") (pintype "passive"))
    )
    (net (code "218") (name "SW0") (class "Default")
      (node (ref "IC1") (pin "1") (pinfunction "G_1") (pintype "input"))
      (node (ref "IC1") (pin "19") (pinfunction "G_19") (pintype "input"))
      (node (ref "IC17") (pin "15") (pinfunction "Y0_15") (pintype "output"))
    )
    (net (code "219") (name "SW1") (class "Default")
      (node (ref "IC17") (pin "14") (pinfunction "Y1_14") (pintype "output"))
      (node (ref "IC2") (pin "1") (pinfunction "G_1") (pintype "input"))
      (node (ref "IC2") (pin "19") (pinfunction "G_19") (pintype "input"))
    )
    (net (code "220") (name "SW2") (class "Default")
      (node (ref "IC17") (pin "13") (pinfunction "Y2_13") (pintype "output"))
      (node (ref "IC3") (pin "1") (pinfunction "G_1") (pintype "input"))
      (node (ref "IC3") (pin "19") (pinfunction "G_19") (pintype "input"))
    )
    (net (code "221") (name "SW3") (class "Default")
      (node (ref "IC17") (pin "12") (pinfunction "Y3_12") (pintype "output"))
      (node (ref "IC4") (pin "1") (pinfunction "G_1") (pintype "input"))
      (node (ref "IC4") (pin "19") (pinfunction "G_19") (pintype "input"))
    )
    (net (code "222") (name "SW4") (class "Default")
      (node (ref "IC17") (pin "11") (pinfunction "Y4_11") (pintype "output"))
      (node (ref "IC5") (pin "1") (pinfunction "G_1") (pintype "input"))
      (node (ref "IC5") (pin "19") (pinfunction "G_19") (pintype "input"))
    )
    (net (code "223") (name "SW5") (class "Default")
      (node (ref "IC17") (pin "10") (pinfunction "Y5_10") (pintype "output"))
      (node (ref "IC6") (pin "1") (pinfunction "G_1") (pintype "input"))
      (node (ref "IC6") (pin "19") (pinfunction "G_19") (pintype "input"))
    )
    (net (code "224") (name "SW6") (class "Default")
      (node (ref "IC17") (pin "9") (pinfunction "Y6_9") (pintype "output"))
      (node (ref "IC7") (pin "1") (pinfunction "G_1") (pintype "input"))
      (node (ref "IC7") (pin "19") (pinfunction "G_19") (pintype "input"))
    )
    (net (code "225") (name "SW7") (class "Default")
      (node (ref "IC17") (pin "7") (pinfunction "Y7_7") (pintype "output"))
      (node (ref "IC8") (pin "1") (pinfunction "G_1") (pintype "input"))
      (node (ref "IC8") (pin "19") (pinfunction "G_19") (pintype "input"))
    )
    (net (code "226") (name "SW8") (class "Default")
      (node (ref "IC18") (pin "15") (pinfunction "Y0_15") (pintype "output"))
      (node (ref "IC9") (pin "1") (pinfunction "G_1") (pintype "input"))
      (node (ref "IC9") (pin "19") (pinfunction "G_19") (pintype "input"))
    )
    (net (code "227") (name "SW9") (class "Default")
      (node (ref "IC10") (pin "1") (pinfunction "G_1") (pintype "input"))
      (node (ref "IC10") (pin "19") (pinfunction "G_19") (pintype "input"))
      (node (ref "IC18") (pin "14") (pinfunction "Y1_14") (pintype "output"))
    )
    (net (code "228") (name "SW10") (class "Default")
      (node (ref "IC11") (pin "1") (pinfunction "G_1") (pintype "input"))
      (node (ref "IC11") (pin "19") (pinfunction "G_19") (pintype "input"))
      (node (ref "IC18") (pin "13") (pinfunction "Y2_13") (pintype "output"))
    )
    (net (code "229") (name "SW11") (class "Default")
      (node (ref "IC12") (pin "1") (pinfunction "G_1") (pintype "input"))
      (node (ref "IC12") (pin "19") (pinfunction "G_19") (pintype "input"))
      (node (ref "IC18") (pin "12") (pinfunction "Y3_12") (pintype "output"))
    )
    (net (code "230") (name "SW12") (class "Default")
      (node (ref "IC13") (pin "1") (pinfunction "G_1") (pintype "input"))
      (node (ref "IC13") (pin "19") (pinfunction "G_19") (pintype "input"))
      (node (ref "IC18") (pin "11") (pinfunction "Y4_11") (pintype "output"))
    )
    (net (code "231") (name "SW13") (class "Default")
      (node (ref "IC14") (pin "1") (pinfunction "G_1") (pintype "input"))
      (node (ref "IC14") (pin "19") (pinfunction "G_19") (pintype "input"))
      (node (ref "IC18") (pin "10") (pinfunction "Y5_10") (pintype "output"))
    )
    (net (code "232") (name "SW14") (class "Default")
      (node (ref "IC15") (pin "1") (pinfunction "G_1") (pintype "input"))
      (node (ref "IC15") (pin "19") (pinfunction "G_19") (pintype "input"))
      (node (ref "IC18") (pin "9") (pinfunction "Y6_9") (pintype "output"))
    )
    (net (code "233") (name "SW15") (class "Default")
      (node (ref "IC16") (pin "1") (pinfunction "G_1") (pintype "input"))
      (node (ref "IC16") (pin "19") (pinfunction "G_19") (pintype "input"))
      (node (ref "IC18") (pin "7") (pinfunction "Y7_7") (pintype "output"))
    )
    (net (code "234") (name "VCC") (class "Default")
      (node (ref "C1") (pin "1") (pinfunction "1_1") (pintype "passive"))
      (node (ref "C10") (pin "1") (pinfunction "1_1") (pintype "passive"))
      (node (ref "C11") (pin "1") (pinfunction "1_1") (pintype "passive"))
      (node (ref "C12") (pin "1") (pinfunction "1_1") (pintype "passive"))
      (node (ref "C13") (pin "1") (pinfunction "1_1") (pintype "passive"))
      (node (ref "C14") (pin "1") (pinfunction "1_1") (pintype "passive"))
      (node (ref "C15") (pin "1") (pinfunction "1_1") (pintype "passive"))
      (node (ref "C16") (pin "1") (pinfunction "1_1") (pintype "passive"))
      (node (ref "C2") (pin "1") (pinfunction "1_1") (pintype "passive"))
      (node (ref "C3") (pin "1") (pinfunction "1_1") (pintype "passive"))
      (node (ref "C4") (pin "1") (pinfunction "1_1") (pintype "passive"))
      (node (ref "C5") (pin "1") (pinfunction "1_1") (pintype "passive"))
      (node (ref "C6") (pin "1") (pinfunction "1_1") (pintype "passive"))
      (node (ref "C7") (pin "1") (pinfunction "1_1") (pintype "passive"))
      (node (ref "C8") (pin "1") (pinfunction "1_1") (pintype "passive"))
      (node (ref "C9") (pin "1") (pinfunction "1_1") (pintype "passive"))
      (node (ref "R2") (pin "2") (pinfunction "2_2") (pintype "passive"))
      (node (ref "RN1") (pin "1") (pinfunction "1_1") (pintype "passive"))
      (node (ref "RN10") (pin "1") (pinfunction "1_1") (pintype "passive"))
      (node (ref "RN11") (pin "1") (pinfunction "1_1") (pintype "passive"))
      (node (ref "RN12") (pin "1") (pinfunction "1_1") (pintype "passive"))
      (node (ref "RN13") (pin "1") (pinfunction "1_1") (pintype "passive"))
      (node (ref "RN14") (pin "1") (pinfunction "1_1") (pintype "passive"))
      (node (ref "RN15") (pin "1") (pinfunction "1_1") (pintype "passive"))
      (node (ref "RN16") (pin "1") (pinfunction "1_1") (pintype "passive"))
      (node (ref "RN2") (pin "1") (pinfunction "1_1") (pintype "passive"))
      (node (ref "RN3") (pin "1") (pinfunction "1_1") (pintype "passive"))
      (node (ref "RN4") (pin "1") (pinfunction "1_1") (pintype "passive"))
      (node (ref "RN5") (pin "1") (pinfunction "1_1") (pintype "passive"))
      (node (ref "RN6") (pin "1") (pinfunction "1_1") (pintype "passive"))
      (node (ref "RN7") (pin "1") (pinfunction "1_1") (pintype "passive"))
      (node (ref "RN8") (pin "1") (pinfunction "1_1") (pintype "passive"))
      (node (ref "RN9") (pin "1") (pinfunction "1_1") (pintype "passive"))
      (node (ref "V1") (pin "14") (pinfunction "+UB_14") (pintype "power_in"))
      (node (ref "X1") (pin "A2") (pinfunction "B_A2") (pintype "passive"))
      (node (ref "X1") (pin "A31") (pinfunction "B_A31") (pintype "passive"))
      (node (ref "X1") (pin "B2") (pinfunction "B_B2") (pintype "passive"))
      (node (ref "X1") (pin "B31") (pinfunction "B_B31") (pintype "passive"))
      (node (ref "X1") (pin "C2") (pinfunction "B_C2") (pintype "passive"))
      (node (ref "X1") (pin "C31") (pinfunction "B_C31") (pintype "passive"))
    )
    (net (code "235") (name "unconnected-(IC21A-Y2-Pad13)") (class "Default")
      (node (ref "IC21") (pin "13") (pinfunction "Y2_13") (pintype "output"))
    )
    (net (code "236") (name "unconnected-(IC21A-Y3-Pad12)") (class "Default")
      (node (ref "IC21") (pin "12") (pinfunction "Y3_12") (pintype "output"))
    )
    (net (code "237") (name "unconnected-(IC21A-Y4-Pad11)") (class "Default")
      (node (ref "IC21") (pin "11") (pinfunction "Y4_11") (pintype "output"))
    )
    (net (code "238") (name "unconnected-(IC21A-Y5-Pad10)") (class "Default")
      (node (ref "IC21") (pin "10") (pinfunction "Y5_10") (pintype "output"))
    )
    (net (code "239") (name "unconnected-(IC21A-Y6-Pad9)") (class "Default")
      (node (ref "IC21") (pin "9") (pinfunction "Y6_9") (pintype "output"))
    )
    (net (code "240") (name "unconnected-(IC21A-Y7-Pad7)") (class "Default")
      (node (ref "IC21") (pin "7") (pinfunction "Y7_7") (pintype "output"))
    )
    (net (code "241") (name "unconnected-(V1C-Y-Pad1)") (class "Default")
      (node (ref "V1") (pin "1") (pinfunction "Y_1") (pintype "output"))
    )
  )
)
